# WidePhoton.net
KiCad netlist of a schematic drawn in EAGLE
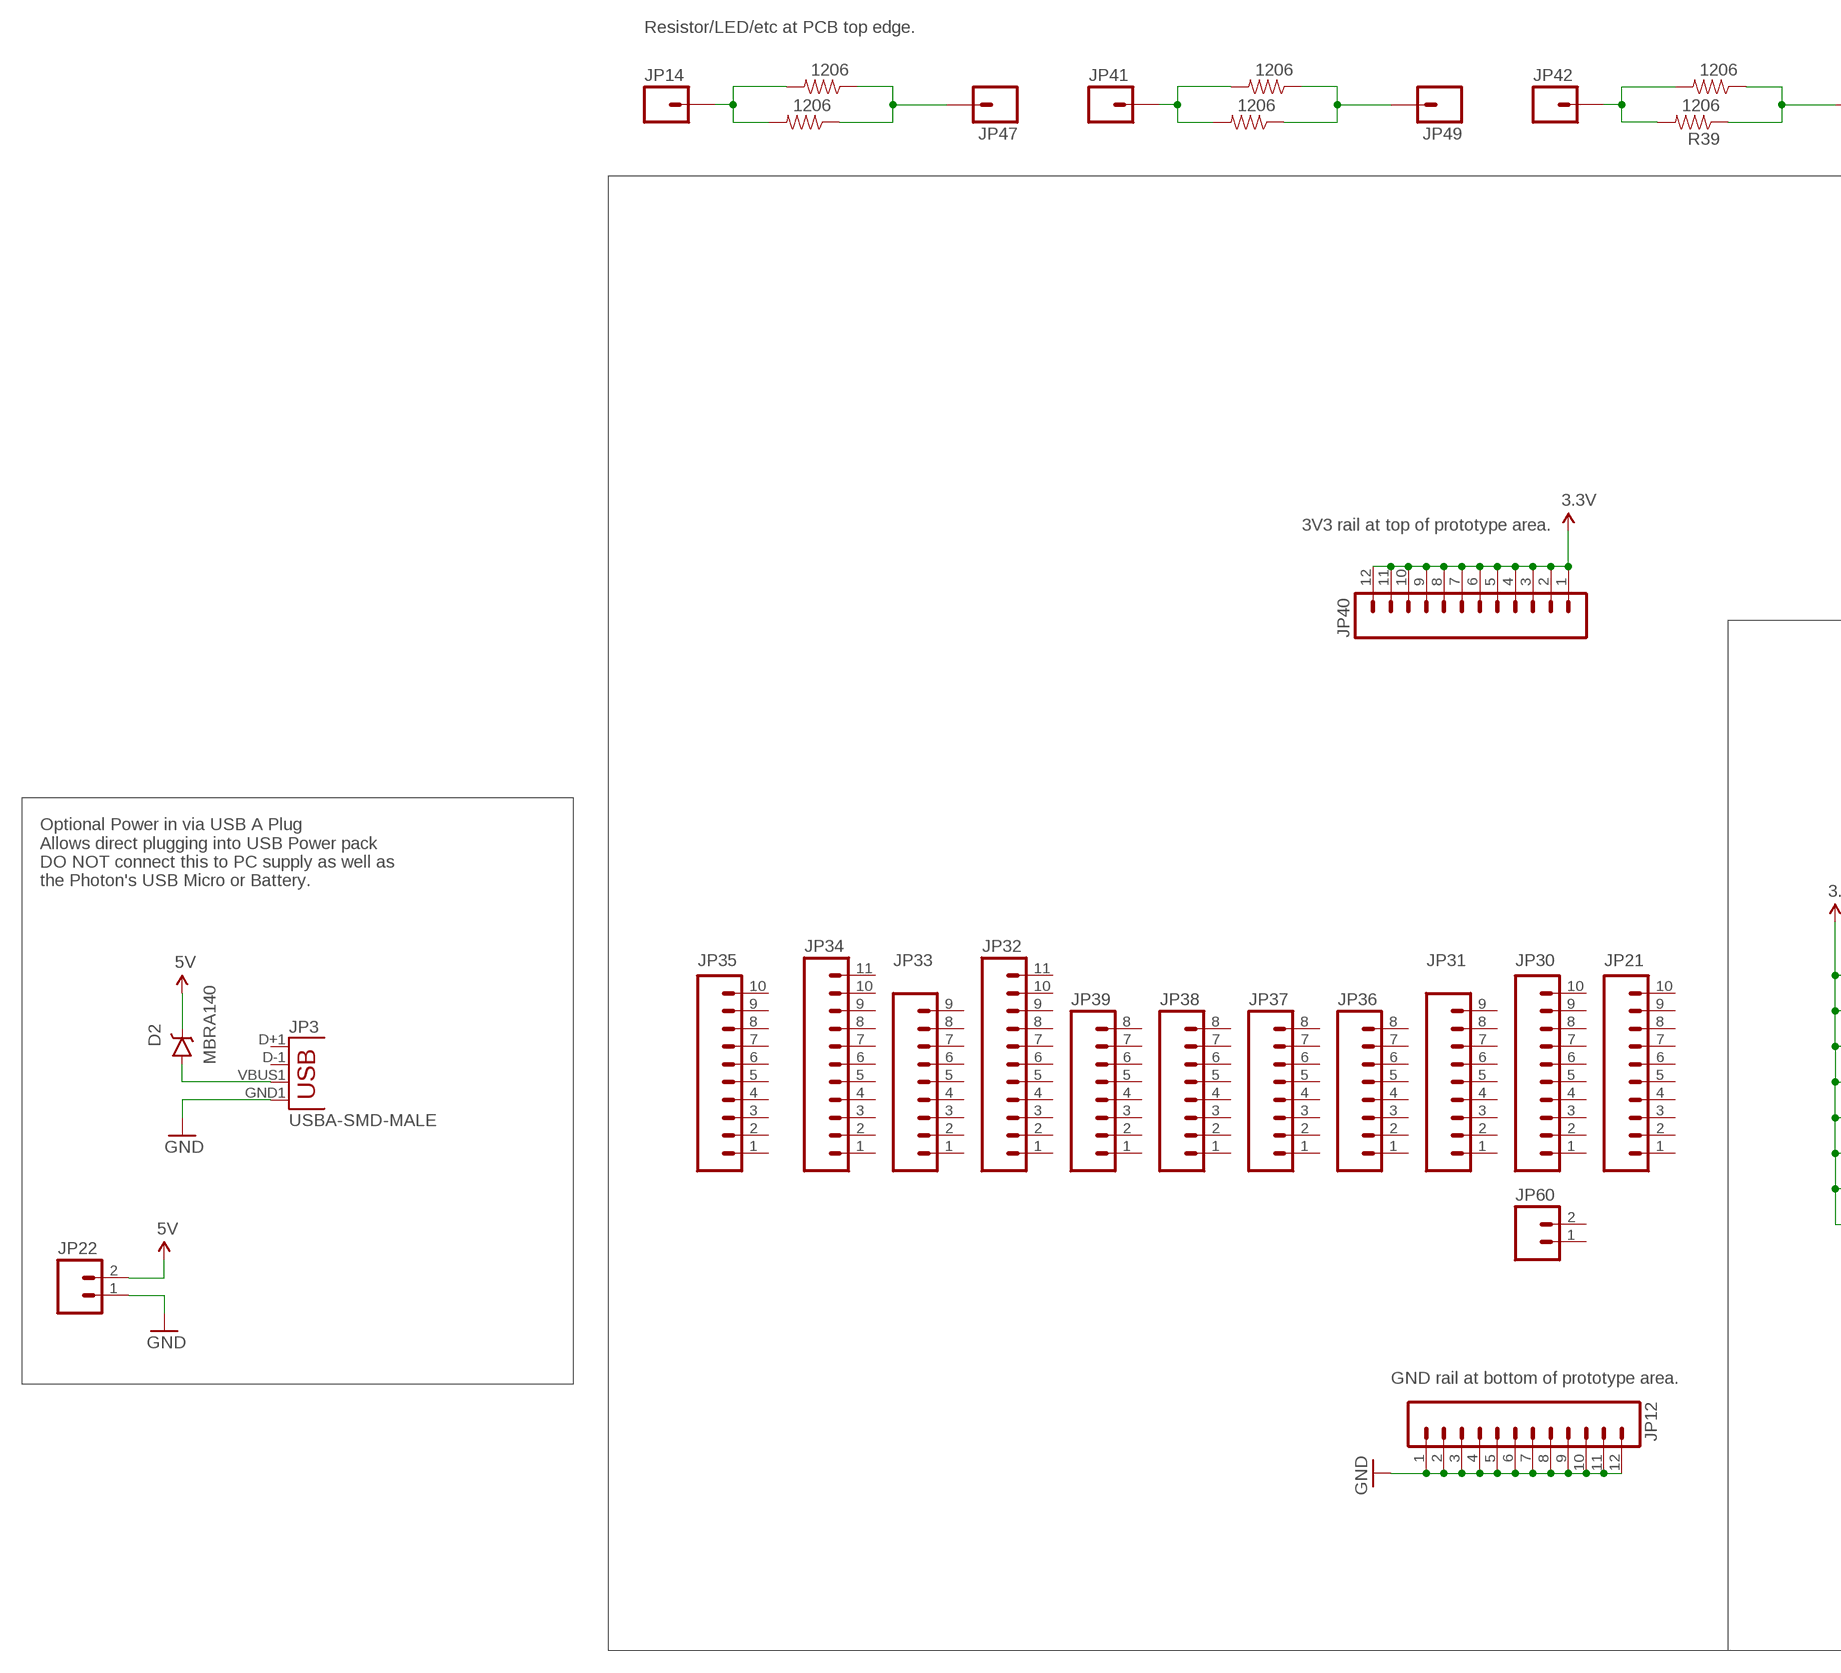
[diagram p0: schematic, sheet 1, part 1 of 2]
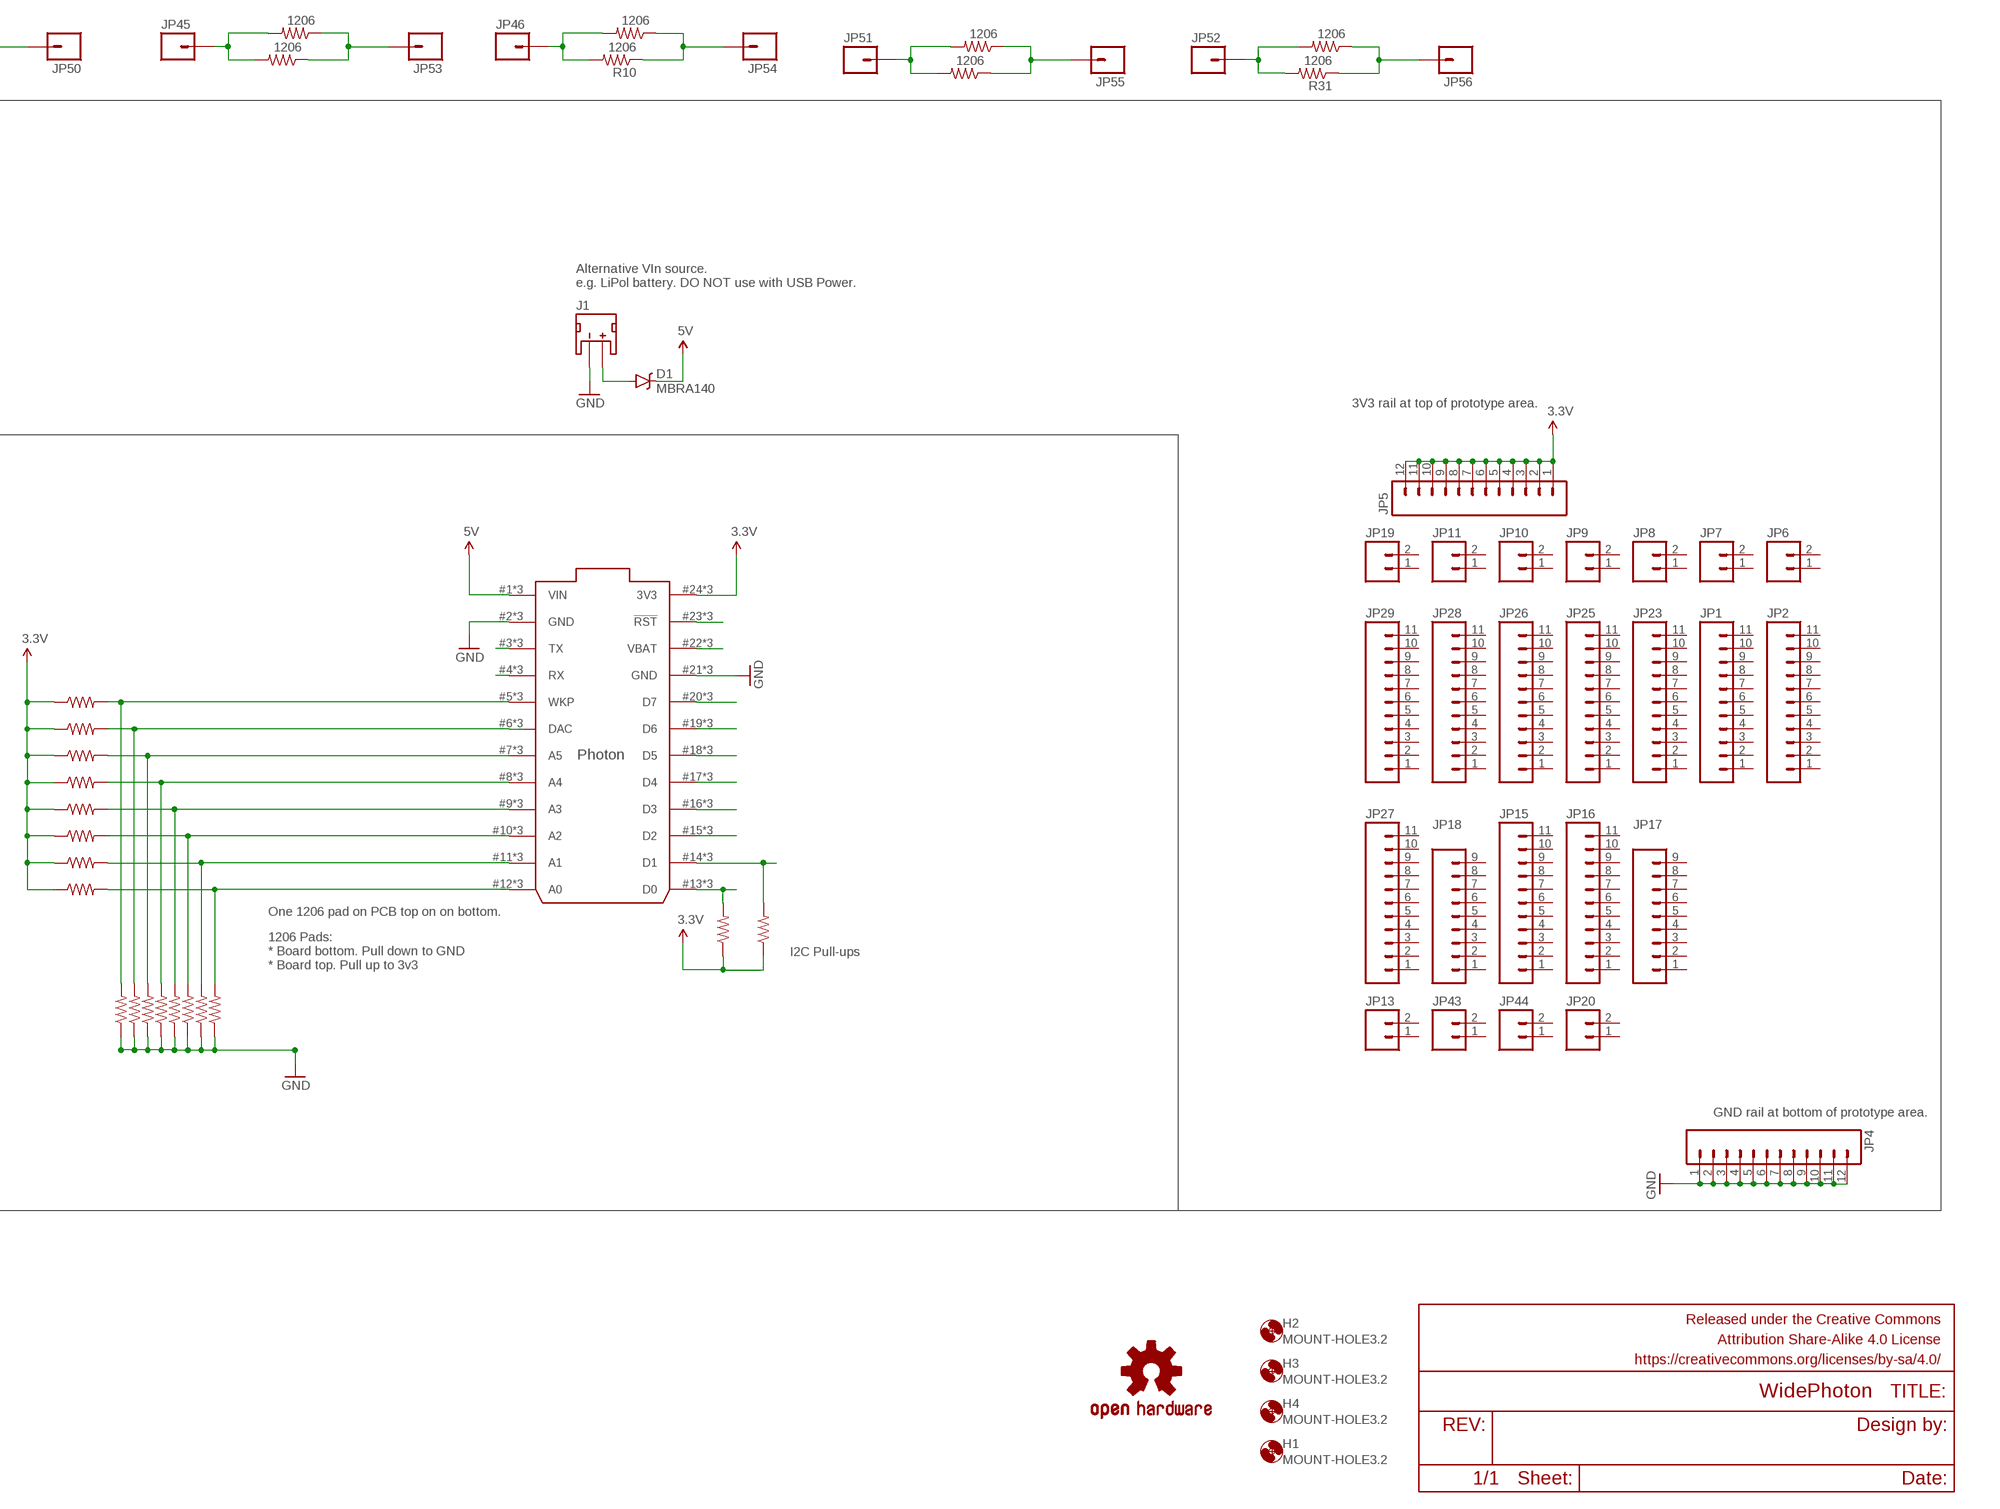
[diagram p1: schematic, sheet 1, part 2 of 2]

(export (version "E")
  (design (tool "Eeschema 10.0.6"))
  (components
    (comp (ref "D1")
      (value "MBRA140")
      (footprint "eagle-import:SMA-DIODE")
      (libsource (lib "eagle-import") (part "MBRA140"))
    )
    (comp (ref "D2")
      (value "MBRA140")
      (footprint "eagle-import:SMA-DIODE")
      (libsource (lib "eagle-import") (part "MBRA140"))
    )
    (comp (ref "FRAME1")
      (value "FRAME-LEDGER")
      (footprint "eagle-import:CREATIVE_COMMONS")
      (libsource (lib "eagle-import") (part "FRAME-LEDGER"))
    )
    (comp (ref "H1")
      (value "MOUNT-HOLE3.2")
      (footprint "eagle-import:3,2")
      (libsource (lib "eagle-import") (part "MOUNT-HOLE3.2"))
    )
    (comp (ref "H2")
      (value "MOUNT-HOLE3.2")
      (footprint "eagle-import:3,2")
      (libsource (lib "eagle-import") (part "MOUNT-HOLE3.2"))
    )
    (comp (ref "H3")
      (value "MOUNT-HOLE3.2")
      (footprint "eagle-import:3,2")
      (libsource (lib "eagle-import") (part "MOUNT-HOLE3.2"))
    )
    (comp (ref "H4")
      (value "MOUNT-HOLE3.2")
      (footprint "eagle-import:3,2")
      (libsource (lib "eagle-import") (part "MOUNT-HOLE3.2"))
    )
    (comp (ref "IC1")
      (value "PHOTON_WITH_STACKABLE_HEADERS")
      (footprint "eagle-import:PHOTON_STACKABLE")
      (libsource (lib "eagle-import") (part "PHOTON_WITH_STACKABLE_HEADERS"))
    )
    (comp (ref "J1")
      (value "JST_2MM_MALE")
      (footprint "eagle-import:JST-2-SMD")
      (libsource (lib "eagle-import") (part "JST_2MM_MALE"))
    )
    (comp (ref "JP1")
      (value "M111X11_NO_SILK")
      (footprint "eagle-import:1X11_NO_SILK")
      (libsource (lib "eagle-import") (part "M111X11_NO_SILK"))
    )
    (comp (ref "JP2")
      (value "M111X11_NO_SILK")
      (footprint "eagle-import:1X11_NO_SILK")
      (libsource (lib "eagle-import") (part "M111X11_NO_SILK"))
    )
    (comp (ref "JP3")
      (value "USBA-SMD-MALE")
      (footprint "eagle-import:USB-A-SMT-MALE")
      (libsource (lib "eagle-import") (part "USBA-SMD-MALE"))
    )
    (comp (ref "JP4")
      (value "M12PTH")
      (footprint "eagle-import:1X12")
      (libsource (lib "eagle-import") (part "M12PTH"))
    )
    (comp (ref "JP5")
      (value "M12PTH")
      (footprint "eagle-import:1X12")
      (libsource (lib "eagle-import") (part "M12PTH"))
    )
    (comp (ref "JP6")
      (value "M021X02_NO_SILK")
      (footprint "eagle-import:1X02_NO_SILK")
      (libsource (lib "eagle-import") (part "M021X02_NO_SILK"))
    )
    (comp (ref "JP7")
      (value "M021X02_NO_SILK")
      (footprint "eagle-import:1X02_NO_SILK")
      (libsource (lib "eagle-import") (part "M021X02_NO_SILK"))
    )
    (comp (ref "JP8")
      (value "M021X02_NO_SILK")
      (footprint "eagle-import:1X02_NO_SILK")
      (libsource (lib "eagle-import") (part "M021X02_NO_SILK"))
    )
    (comp (ref "JP9")
      (value "M021X02_NO_SILK")
      (footprint "eagle-import:1X02_NO_SILK")
      (libsource (lib "eagle-import") (part "M021X02_NO_SILK"))
    )
    (comp (ref "JP10")
      (value "M021X02_NO_SILK")
      (footprint "eagle-import:1X02_NO_SILK")
      (libsource (lib "eagle-import") (part "M021X02_NO_SILK"))
    )
    (comp (ref "JP11")
      (value "M021X02_NO_SILK")
      (footprint "eagle-import:1X02_NO_SILK")
      (libsource (lib "eagle-import") (part "M021X02_NO_SILK"))
    )
    (comp (ref "JP12")
      (value "M12PTH")
      (footprint "eagle-import:1X12")
      (libsource (lib "eagle-import") (part "M12PTH"))
    )
    (comp (ref "JP13")
      (value "M021X02_NO_SILK")
      (footprint "eagle-import:1X02_NO_SILK")
      (libsource (lib "eagle-import") (part "M021X02_NO_SILK"))
    )
    (comp (ref "JP14")
      (value "M01PTH")
      (footprint "eagle-import:1X01")
      (libsource (lib "eagle-import") (part "M01PTH"))
    )
    (comp (ref "JP15")
      (value "M111X11_NO_SILK")
      (footprint "eagle-import:1X11_NO_SILK")
      (libsource (lib "eagle-import") (part "M111X11_NO_SILK"))
    )
    (comp (ref "JP16")
      (value "M111X11_NO_SILK")
      (footprint "eagle-import:1X11_NO_SILK")
      (libsource (lib "eagle-import") (part "M111X11_NO_SILK"))
    )
    (comp (ref "JP17")
      (value "M09NO_SILK")
      (footprint "eagle-import:1X09_NO_SILK")
      (libsource (lib "eagle-import") (part "M09NO_SILK"))
    )
    (comp (ref "JP18")
      (value "M09NO_SILK")
      (footprint "eagle-import:1X09_NO_SILK")
      (libsource (lib "eagle-import") (part "M09NO_SILK"))
    )
    (comp (ref "JP19")
      (value "M021X02_NO_SILK")
      (footprint "eagle-import:1X02_NO_SILK")
      (libsource (lib "eagle-import") (part "M021X02_NO_SILK"))
    )
    (comp (ref "JP20")
      (value "M021X02_NO_SILK")
      (footprint "eagle-import:1X02_NO_SILK")
      (libsource (lib "eagle-import") (part "M021X02_NO_SILK"))
    )
    (comp (ref "JP21")
      (value "M10NO_SILK_PTH_FEMALE")
      (footprint "eagle-import:1X10_NO_SILK")
      (libsource (lib "eagle-import") (part "M10NO_SILK_PTH_FEMALE"))
    )
    (comp (ref "JP22")
      (value "M021X02_NO_SILK")
      (footprint "eagle-import:1X02_NO_SILK")
      (libsource (lib "eagle-import") (part "M021X02_NO_SILK"))
    )
    (comp (ref "JP23")
      (value "M111X11_NO_SILK")
      (footprint "eagle-import:1X11_NO_SILK")
      (libsource (lib "eagle-import") (part "M111X11_NO_SILK"))
    )
    (comp (ref "JP25")
      (value "M111X11_NO_SILK")
      (footprint "eagle-import:1X11_NO_SILK")
      (libsource (lib "eagle-import") (part "M111X11_NO_SILK"))
    )
    (comp (ref "JP26")
      (value "M111X11_NO_SILK")
      (footprint "eagle-import:1X11_NO_SILK")
      (libsource (lib "eagle-import") (part "M111X11_NO_SILK"))
    )
    (comp (ref "JP27")
      (value "M111X11_NO_SILK")
      (footprint "eagle-import:1X11_NO_SILK")
      (libsource (lib "eagle-import") (part "M111X11_NO_SILK"))
    )
    (comp (ref "JP28")
      (value "M111X11_NO_SILK")
      (footprint "eagle-import:1X11_NO_SILK")
      (libsource (lib "eagle-import") (part "M111X11_NO_SILK"))
    )
    (comp (ref "JP29")
      (value "M111X11_NO_SILK")
      (footprint "eagle-import:1X11_NO_SILK")
      (libsource (lib "eagle-import") (part "M111X11_NO_SILK"))
    )
    (comp (ref "JP30")
      (value "M10NO_SILK_PTH_FEMALE")
      (footprint "eagle-import:1X10_NO_SILK")
      (libsource (lib "eagle-import") (part "M10NO_SILK_PTH_FEMALE"))
    )
    (comp (ref "JP31")
      (value "M09NO_SILK")
      (footprint "eagle-import:1X09_NO_SILK")
      (libsource (lib "eagle-import") (part "M09NO_SILK"))
    )
    (comp (ref "JP32")
      (value "M111X11_NO_SILK")
      (footprint "eagle-import:1X11_NO_SILK")
      (libsource (lib "eagle-import") (part "M111X11_NO_SILK"))
    )
    (comp (ref "JP33")
      (value "M09NO_SILK")
      (footprint "eagle-import:1X09_NO_SILK")
      (libsource (lib "eagle-import") (part "M09NO_SILK"))
    )
    (comp (ref "JP34")
      (value "M111X11_NO_SILK")
      (footprint "eagle-import:1X11_NO_SILK")
      (libsource (lib "eagle-import") (part "M111X11_NO_SILK"))
    )
    (comp (ref "JP35")
      (value "M10NO_SILK_PTH_FEMALE")
      (footprint "eagle-import:1X10_NO_SILK")
      (libsource (lib "eagle-import") (part "M10NO_SILK_PTH_FEMALE"))
    )
    (comp (ref "JP36")
      (value "M08NO_SILK_FEMALE_PTH")
      (footprint "eagle-import:1X08_NO_SILK")
      (libsource (lib "eagle-import") (part "M08NO_SILK_FEMALE_PTH"))
    )
    (comp (ref "JP37")
      (value "M08NO_SILK_FEMALE_PTH")
      (footprint "eagle-import:1X08_NO_SILK")
      (libsource (lib "eagle-import") (part "M08NO_SILK_FEMALE_PTH"))
    )
    (comp (ref "JP38")
      (value "M08NO_SILK_FEMALE_PTH")
      (footprint "eagle-import:1X08_NO_SILK")
      (libsource (lib "eagle-import") (part "M08NO_SILK_FEMALE_PTH"))
    )
    (comp (ref "JP39")
      (value "M08NO_SILK_FEMALE_PTH")
      (footprint "eagle-import:1X08_NO_SILK")
      (libsource (lib "eagle-import") (part "M08NO_SILK_FEMALE_PTH"))
    )
    (comp (ref "JP40")
      (value "M12PTH")
      (footprint "eagle-import:1X12")
      (libsource (lib "eagle-import") (part "M12PTH"))
    )
    (comp (ref "JP41")
      (value "M01PTH")
      (footprint "eagle-import:1X01")
      (libsource (lib "eagle-import") (part "M01PTH"))
    )
    (comp (ref "JP42")
      (value "M01PTH")
      (footprint "eagle-import:1X01")
      (libsource (lib "eagle-import") (part "M01PTH"))
    )
    (comp (ref "JP43")
      (value "M021X02_NO_SILK")
      (footprint "eagle-import:1X02_NO_SILK")
      (libsource (lib "eagle-import") (part "M021X02_NO_SILK"))
    )
    (comp (ref "JP44")
      (value "M021X02_NO_SILK")
      (footprint "eagle-import:1X02_NO_SILK")
      (libsource (lib "eagle-import") (part "M021X02_NO_SILK"))
    )
    (comp (ref "JP45")
      (value "M01PTH")
      (footprint "eagle-import:1X01")
      (libsource (lib "eagle-import") (part "M01PTH"))
    )
    (comp (ref "JP46")
      (value "M01PTH")
      (footprint "eagle-import:1X01")
      (libsource (lib "eagle-import") (part "M01PTH"))
    )
    (comp (ref "JP47")
      (value "M01PTH")
      (footprint "eagle-import:1X01")
      (libsource (lib "eagle-import") (part "M01PTH"))
    )
    (comp (ref "JP49")
      (value "M01PTH")
      (footprint "eagle-import:1X01")
      (libsource (lib "eagle-import") (part "M01PTH"))
    )
    (comp (ref "JP50")
      (value "M01PTH")
      (footprint "eagle-import:1X01")
      (libsource (lib "eagle-import") (part "M01PTH"))
    )
    (comp (ref "JP51")
      (value "M01PTH")
      (footprint "eagle-import:1X01")
      (libsource (lib "eagle-import") (part "M01PTH"))
    )
    (comp (ref "JP52")
      (value "M01PTH")
      (footprint "eagle-import:1X01")
      (libsource (lib "eagle-import") (part "M01PTH"))
    )
    (comp (ref "JP53")
      (value "M01PTH")
      (footprint "eagle-import:1X01")
      (libsource (lib "eagle-import") (part "M01PTH"))
    )
    (comp (ref "JP54")
      (value "M01PTH")
      (footprint "eagle-import:1X01")
      (libsource (lib "eagle-import") (part "M01PTH"))
    )
    (comp (ref "JP55")
      (value "M01PTH")
      (footprint "eagle-import:1X01")
      (libsource (lib "eagle-import") (part "M01PTH"))
    )
    (comp (ref "JP56")
      (value "M01PTH")
      (footprint "eagle-import:1X01")
      (libsource (lib "eagle-import") (part "M01PTH"))
    )
    (comp (ref "JP60")
      (value "M021X02_NO_SILK")
      (footprint "eagle-import:1X02_NO_SILK")
      (libsource (lib "eagle-import") (part "M021X02_NO_SILK"))
    )
    (comp (ref "LOGO1")
      (value "OSHW-LOGOM")
      (footprint "eagle-import:OSHW-LOGO-M")
      (libsource (lib "eagle-import") (part "OSHW-LOGOM"))
    )
    (comp (ref "R1")
      (value "1206")
      (footprint "eagle-import:1206")
      (libsource (lib "eagle-import") (part "RESISTOR1206"))
    )
    (comp (ref "R2")
      (value "1206")
      (footprint "eagle-import:1206")
      (libsource (lib "eagle-import") (part "RESISTOR1206"))
    )
    (comp (ref "R3")
      (value "1206")
      (footprint "eagle-import:1206")
      (libsource (lib "eagle-import") (part "RESISTOR1206"))
    )
    (comp (ref "R4")
      (value "1206")
      (footprint "eagle-import:1206")
      (libsource (lib "eagle-import") (part "RESISTOR1206"))
    )
    (comp (ref "R5")
      (value "1206")
      (footprint "eagle-import:1206")
      (libsource (lib "eagle-import") (part "RESISTOR1206"))
    )
    (comp (ref "R6")
      (value "1206")
      (footprint "eagle-import:1206")
      (libsource (lib "eagle-import") (part "RESISTOR1206"))
    )
    (comp (ref "R7")
      (value "1206")
      (footprint "eagle-import:1206")
      (libsource (lib "eagle-import") (part "RESISTOR1206"))
    )
    (comp (ref "R8")
      (value "1206")
      (footprint "eagle-import:1206")
      (libsource (lib "eagle-import") (part "RESISTOR1206"))
    )
    (comp (ref "R9")
      (value "1206")
      (footprint "eagle-import:1206")
      (libsource (lib "eagle-import") (part "RESISTOR1206"))
    )
    (comp (ref "R10")
      (value "1206")
      (footprint "eagle-import:1206")
      (libsource (lib "eagle-import") (part "RESISTOR1206"))
    )
    (comp (ref "R12")
      (value "1206")
      (footprint "eagle-import:1206")
      (libsource (lib "eagle-import") (part "RESISTOR1206"))
    )
    (comp (ref "R13")
      (value "1206")
      (footprint "eagle-import:1206")
      (libsource (lib "eagle-import") (part "RESISTOR1206"))
    )
    (comp (ref "R14")
      (value "1206")
      (footprint "eagle-import:1206")
      (libsource (lib "eagle-import") (part "RESISTOR1206"))
    )
    (comp (ref "R15")
      (value "1206")
      (footprint "eagle-import:1206")
      (libsource (lib "eagle-import") (part "RESISTOR1206"))
    )
    (comp (ref "R16")
      (value "1206")
      (footprint "eagle-import:1206")
      (libsource (lib "eagle-import") (part "RESISTOR1206"))
    )
    (comp (ref "R17")
      (value "1206")
      (footprint "eagle-import:1206")
      (libsource (lib "eagle-import") (part "RESISTOR1206"))
    )
    (comp (ref "R19")
      (value "1206")
      (footprint "eagle-import:1206")
      (libsource (lib "eagle-import") (part "RESISTOR1206"))
    )
    (comp (ref "R20")
      (value "1206")
      (footprint "eagle-import:1206")
      (libsource (lib "eagle-import") (part "RESISTOR1206"))
    )
    (comp (ref "R21")
      (value "1206")
      (footprint "eagle-import:1206")
      (libsource (lib "eagle-import") (part "RESISTOR1206"))
    )
    (comp (ref "R22")
      (value "1206")
      (footprint "eagle-import:1206")
      (libsource (lib "eagle-import") (part "RESISTOR1206"))
    )
    (comp (ref "R24")
      (value "1206")
      (footprint "eagle-import:1206")
      (libsource (lib "eagle-import") (part "RESISTOR1206"))
    )
    (comp (ref "R30")
      (value "1206")
      (footprint "eagle-import:1206")
      (libsource (lib "eagle-import") (part "RESISTOR1206"))
    )
    (comp (ref "R31")
      (value "1206")
      (footprint "eagle-import:1206")
      (libsource (lib "eagle-import") (part "RESISTOR1206"))
    )
    (comp (ref "R32")
      (value "1206")
      (footprint "eagle-import:1206")
      (libsource (lib "eagle-import") (part "RESISTOR1206"))
    )
    (comp (ref "R34")
      (value "1206")
      (footprint "eagle-import:1206")
      (libsource (lib "eagle-import") (part "RESISTOR1206"))
    )
    (comp (ref "R35")
      (value "1206")
      (footprint "eagle-import:1206")
      (libsource (lib "eagle-import") (part "RESISTOR1206"))
    )
    (comp (ref "R36")
      (value "1206")
      (footprint "eagle-import:1206")
      (libsource (lib "eagle-import") (part "RESISTOR1206"))
    )
    (comp (ref "R37")
      (value "1206")
      (footprint "eagle-import:1206")
      (libsource (lib "eagle-import") (part "RESISTOR1206"))
    )
    (comp (ref "R39")
      (value "1206")
      (footprint "eagle-import:1206")
      (libsource (lib "eagle-import") (part "RESISTOR1206"))
    )
    (comp (ref "R40")
      (value "1206")
      (footprint "eagle-import:1206")
      (libsource (lib "eagle-import") (part "RESISTOR1206"))
    )
    (comp (ref "R41")
      (value "1206")
      (footprint "eagle-import:1206")
      (libsource (lib "eagle-import") (part "RESISTOR1206"))
    )
    (comp (ref "R44")
      (value "1206")
      (footprint "eagle-import:1206")
      (libsource (lib "eagle-import") (part "RESISTOR1206"))
    )
  )
  (nets
    (net (code "1") (name "3.3V") (class "Default")
      (node (ref "IC1") (pin "#24") (pinfunction "3V3_#24") (pintype "power_in"))
      (node (ref "IC1") (pin "24") (pinfunction "3V3_24") (pintype "power_in"))
      (node (ref "IC1") (pin "@24") (pinfunction "3V3_@24") (pintype "power_in"))
      (node (ref "JP40") (pin "1") (pinfunction "1_1") (pintype "passive"))
      (node (ref "JP40") (pin "10") (pinfunction "10_10") (pintype "passive"))
      (node (ref "JP40") (pin "11") (pinfunction "11_11") (pintype "passive"))
      (node (ref "JP40") (pin "12") (pinfunction "12_12") (pintype "passive"))
      (node (ref "JP40") (pin "2") (pinfunction "2_2") (pintype "passive"))
      (node (ref "JP40") (pin "3") (pinfunction "3_3") (pintype "passive"))
      (node (ref "JP40") (pin "4") (pinfunction "4_4") (pintype "passive"))
      (node (ref "JP40") (pin "5") (pinfunction "5_5") (pintype "passive"))
      (node (ref "JP40") (pin "6") (pinfunction "6_6") (pintype "passive"))
      (node (ref "JP40") (pin "7") (pinfunction "7_7") (pintype "passive"))
      (node (ref "JP40") (pin "8") (pinfunction "8_8") (pintype "passive"))
      (node (ref "JP40") (pin "9") (pinfunction "9_9") (pintype "passive"))
      (node (ref "JP5") (pin "1") (pinfunction "1_1") (pintype "passive"))
      (node (ref "JP5") (pin "10") (pinfunction "10_10") (pintype "passive"))
      (node (ref "JP5") (pin "11") (pinfunction "11_11") (pintype "passive"))
      (node (ref "JP5") (pin "12") (pinfunction "12_12") (pintype "passive"))
      (node (ref "JP5") (pin "2") (pinfunction "2_2") (pintype "passive"))
      (node (ref "JP5") (pin "3") (pinfunction "3_3") (pintype "passive"))
      (node (ref "JP5") (pin "4") (pinfunction "4_4") (pintype "passive"))
      (node (ref "JP5") (pin "5") (pinfunction "5_5") (pintype "passive"))
      (node (ref "JP5") (pin "6") (pinfunction "6_6") (pintype "passive"))
      (node (ref "JP5") (pin "7") (pinfunction "7_7") (pintype "passive"))
      (node (ref "JP5") (pin "8") (pinfunction "8_8") (pintype "passive"))
      (node (ref "JP5") (pin "9") (pinfunction "9_9") (pintype "passive"))
      (node (ref "R1") (pin "1") (pinfunction "1_1") (pintype "passive"))
      (node (ref "R12") (pin "1") (pinfunction "1_1") (pintype "passive"))
      (node (ref "R15") (pin "1") (pinfunction "1_1") (pintype "passive"))
      (node (ref "R2") (pin "1") (pinfunction "1_1") (pintype "passive"))
      (node (ref "R3") (pin "1") (pinfunction "1_1") (pintype "passive"))
      (node (ref "R4") (pin "1") (pinfunction "1_1") (pintype "passive"))
      (node (ref "R5") (pin "1") (pinfunction "1_1") (pintype "passive"))
      (node (ref "R6") (pin "1") (pinfunction "1_1") (pintype "passive"))
      (node (ref "R7") (pin "1") (pinfunction "1_1") (pintype "passive"))
      (node (ref "R9") (pin "1") (pinfunction "1_1") (pintype "passive"))
    )
    (net (code "2") (name "5V") (class "Default")
      (node (ref "D1") (pin "C") (pinfunction "C_C") (pintype "passive"))
      (node (ref "D2") (pin "C") (pinfunction "C_C") (pintype "passive"))
      (node (ref "IC1") (pin "#1") (pinfunction "VIN_#1") (pintype "power_in"))
      (node (ref "IC1") (pin "1") (pinfunction "VIN_1") (pintype "power_in"))
      (node (ref "IC1") (pin "@1") (pinfunction "VIN_@1") (pintype "power_in"))
      (node (ref "JP22") (pin "2") (pinfunction "2_2") (pintype "passive"))
    )
    (net (code "3") (name "GND") (class "Default")
      (node (ref "IC1") (pin "#2") (pinfunction "GND_#2") (pintype "power_in"))
      (node (ref "IC1") (pin "#21") (pinfunction "GND_#21") (pintype "power_in"))
      (node (ref "IC1") (pin "2") (pinfunction "GND_2") (pintype "power_in"))
      (node (ref "IC1") (pin "21") (pinfunction "GND_21") (pintype "power_in"))
      (node (ref "IC1") (pin "@2") (pinfunction "GND_@2") (pintype "power_in"))
      (node (ref "IC1") (pin "@21") (pinfunction "GND_@21") (pintype "power_in"))
      (node (ref "J1") (pin "1") (pinfunction "-_1") (pintype "bidirectional"))
      (node (ref "JP12") (pin "1") (pinfunction "1_1") (pintype "passive"))
      (node (ref "JP12") (pin "10") (pinfunction "10_10") (pintype "passive"))
      (node (ref "JP12") (pin "11") (pinfunction "11_11") (pintype "passive"))
      (node (ref "JP12") (pin "12") (pinfunction "12_12") (pintype "passive"))
      (node (ref "JP12") (pin "2") (pinfunction "2_2") (pintype "passive"))
      (node (ref "JP12") (pin "3") (pinfunction "3_3") (pintype "passive"))
      (node (ref "JP12") (pin "4") (pinfunction "4_4") (pintype "passive"))
      (node (ref "JP12") (pin "5") (pinfunction "5_5") (pintype "passive"))
      (node (ref "JP12") (pin "6") (pinfunction "6_6") (pintype "passive"))
      (node (ref "JP12") (pin "7") (pinfunction "7_7") (pintype "passive"))
      (node (ref "JP12") (pin "8") (pinfunction "8_8") (pintype "passive"))
      (node (ref "JP12") (pin "9") (pinfunction "9_9") (pintype "passive"))
      (node (ref "JP22") (pin "1") (pinfunction "1_1") (pintype "passive"))
      (node (ref "JP3") (pin "GND1") (pinfunction "GND_GND1") (pintype "bidirectional"))
      (node (ref "JP4") (pin "1") (pinfunction "1_1") (pintype "passive"))
      (node (ref "JP4") (pin "10") (pinfunction "10_10") (pintype "passive"))
      (node (ref "JP4") (pin "11") (pinfunction "11_11") (pintype "passive"))
      (node (ref "JP4") (pin "12") (pinfunction "12_12") (pintype "passive"))
      (node (ref "JP4") (pin "2") (pinfunction "2_2") (pintype "passive"))
      (node (ref "JP4") (pin "3") (pinfunction "3_3") (pintype "passive"))
      (node (ref "JP4") (pin "4") (pinfunction "4_4") (pintype "passive"))
      (node (ref "JP4") (pin "5") (pinfunction "5_5") (pintype "passive"))
      (node (ref "JP4") (pin "6") (pinfunction "6_6") (pintype "passive"))
      (node (ref "JP4") (pin "7") (pinfunction "7_7") (pintype "passive"))
      (node (ref "JP4") (pin "8") (pinfunction "8_8") (pintype "passive"))
      (node (ref "JP4") (pin "9") (pinfunction "9_9") (pintype "passive"))
      (node (ref "R13") (pin "1") (pinfunction "1_1") (pintype "passive"))
      (node (ref "R14") (pin "1") (pinfunction "1_1") (pintype "passive"))
      (node (ref "R16") (pin "1") (pinfunction "1_1") (pintype "passive"))
      (node (ref "R19") (pin "1") (pinfunction "1_1") (pintype "passive"))
      (node (ref "R20") (pin "1") (pinfunction "1_1") (pintype "passive"))
      (node (ref "R21") (pin "1") (pinfunction "1_1") (pintype "passive"))
      (node (ref "R22") (pin "1") (pinfunction "1_1") (pintype "passive"))
      (node (ref "R8") (pin "1") (pinfunction "1_1") (pintype "passive"))
    )
    (net (code "4") (name "Net-(IC1-A0-Pad#12)") (class "Default")
      (node (ref "IC1") (pin "#12") (pinfunction "A0_#12") (pintype "bidirectional"))
      (node (ref "IC1") (pin "12") (pinfunction "A0_12") (pintype "bidirectional"))
      (node (ref "IC1") (pin "@12") (pinfunction "A0_@12") (pintype "bidirectional"))
      (node (ref "R22") (pin "2") (pinfunction "2_2") (pintype "passive"))
      (node (ref "R7") (pin "2") (pinfunction "2_2") (pintype "passive"))
    )
    (net (code "5") (name "Net-(IC1-A1-Pad#11)") (class "Default")
      (node (ref "IC1") (pin "#11") (pinfunction "A1_#11") (pintype "bidirectional"))
      (node (ref "IC1") (pin "11") (pinfunction "A1_11") (pintype "bidirectional"))
      (node (ref "IC1") (pin "@11") (pinfunction "A1_@11") (pintype "bidirectional"))
      (node (ref "R21") (pin "2") (pinfunction "2_2") (pintype "passive"))
      (node (ref "R6") (pin "2") (pinfunction "2_2") (pintype "passive"))
    )
    (net (code "6") (name "Net-(IC1-A2-Pad#10)") (class "Default")
      (node (ref "IC1") (pin "#10") (pinfunction "A2_#10") (pintype "bidirectional"))
      (node (ref "IC1") (pin "10") (pinfunction "A2_10") (pintype "bidirectional"))
      (node (ref "IC1") (pin "@10") (pinfunction "A2_@10") (pintype "bidirectional"))
      (node (ref "R20") (pin "2") (pinfunction "2_2") (pintype "passive"))
      (node (ref "R4") (pin "2") (pinfunction "2_2") (pintype "passive"))
    )
    (net (code "7") (name "Net-(IC1-A3-Pad#9)") (class "Default")
      (node (ref "IC1") (pin "#9") (pinfunction "A3_#9") (pintype "bidirectional"))
      (node (ref "IC1") (pin "9") (pinfunction "A3_9") (pintype "bidirectional"))
      (node (ref "IC1") (pin "@9") (pinfunction "A3_@9") (pintype "bidirectional"))
      (node (ref "R19") (pin "2") (pinfunction "2_2") (pintype "passive"))
      (node (ref "R3") (pin "2") (pinfunction "2_2") (pintype "passive"))
    )
    (net (code "8") (name "Net-(IC1-A4-Pad#8)") (class "Default")
      (node (ref "IC1") (pin "#8") (pinfunction "A4_#8") (pintype "bidirectional"))
      (node (ref "IC1") (pin "8") (pinfunction "A4_8") (pintype "bidirectional"))
      (node (ref "IC1") (pin "@8") (pinfunction "A4_@8") (pintype "bidirectional"))
      (node (ref "R14") (pin "2") (pinfunction "2_2") (pintype "passive"))
      (node (ref "R2") (pin "2") (pinfunction "2_2") (pintype "passive"))
    )
    (net (code "9") (name "Net-(IC1-A5-Pad#7)") (class "Default")
      (node (ref "IC1") (pin "#7") (pinfunction "A5_#7") (pintype "bidirectional"))
      (node (ref "IC1") (pin "7") (pinfunction "A5_7") (pintype "bidirectional"))
      (node (ref "IC1") (pin "@7") (pinfunction "A5_@7") (pintype "bidirectional"))
      (node (ref "R1") (pin "2") (pinfunction "2_2") (pintype "passive"))
      (node (ref "R13") (pin "2") (pinfunction "2_2") (pintype "passive"))
    )
    (net (code "10") (name "Net-(IC1-D0-Pad#13)") (class "Default")
      (node (ref "IC1") (pin "#13") (pinfunction "D0_#13") (pintype "bidirectional"))
      (node (ref "IC1") (pin "13") (pinfunction "D0_13") (pintype "bidirectional"))
      (node (ref "IC1") (pin "@13") (pinfunction "D0_@13") (pintype "bidirectional"))
      (node (ref "R5") (pin "2") (pinfunction "2_2") (pintype "passive"))
    )
    (net (code "11") (name "Net-(IC1-D1-Pad#14)") (class "Default")
      (node (ref "IC1") (pin "#14") (pinfunction "D1_#14") (pintype "bidirectional"))
      (node (ref "IC1") (pin "14") (pinfunction "D1_14") (pintype "bidirectional"))
      (node (ref "IC1") (pin "@14") (pinfunction "D1_@14") (pintype "bidirectional"))
      (node (ref "R9") (pin "2") (pinfunction "2_2") (pintype "passive"))
    )
    (net (code "12") (name "Net-(IC1-D2-Pad#15)") (class "Default")
      (node (ref "IC1") (pin "#15") (pinfunction "D2_#15") (pintype "bidirectional"))
      (node (ref "IC1") (pin "15") (pinfunction "D2_15") (pintype "bidirectional"))
      (node (ref "IC1") (pin "@15") (pinfunction "D2_@15") (pintype "bidirectional"))
    )
    (net (code "13") (name "Net-(IC1-D3-Pad#16)") (class "Default")
      (node (ref "IC1") (pin "#16") (pinfunction "D3_#16") (pintype "bidirectional"))
      (node (ref "IC1") (pin "16") (pinfunction "D3_16") (pintype "bidirectional"))
      (node (ref "IC1") (pin "@16") (pinfunction "D3_@16") (pintype "bidirectional"))
    )
    (net (code "14") (name "Net-(IC1-D4-Pad#17)") (class "Default")
      (node (ref "IC1") (pin "#17") (pinfunction "D4_#17") (pintype "bidirectional"))
      (node (ref "IC1") (pin "17") (pinfunction "D4_17") (pintype "bidirectional"))
      (node (ref "IC1") (pin "@17") (pinfunction "D4_@17") (pintype "bidirectional"))
    )
    (net (code "15") (name "Net-(IC1-D5-Pad#18)") (class "Default")
      (node (ref "IC1") (pin "#18") (pinfunction "D5_#18") (pintype "bidirectional"))
      (node (ref "IC1") (pin "18") (pinfunction "D5_18") (pintype "bidirectional"))
      (node (ref "IC1") (pin "@18") (pinfunction "D5_@18") (pintype "bidirectional"))
    )
    (net (code "16") (name "Net-(IC1-D6-Pad#19)") (class "Default")
      (node (ref "IC1") (pin "#19") (pinfunction "D6_#19") (pintype "bidirectional"))
      (node (ref "IC1") (pin "19") (pinfunction "D6_19") (pintype "bidirectional"))
      (node (ref "IC1") (pin "@19") (pinfunction "D6_@19") (pintype "bidirectional"))
    )
    (net (code "17") (name "Net-(IC1-D7-Pad#20)") (class "Default")
      (node (ref "IC1") (pin "#20") (pinfunction "D7_#20") (pintype "bidirectional"))
      (node (ref "IC1") (pin "20") (pinfunction "D7_20") (pintype "bidirectional"))
      (node (ref "IC1") (pin "@20") (pinfunction "D7_@20") (pintype "bidirectional"))
    )
    (net (code "18") (name "Net-(IC1-DAC-Pad#6)") (class "Default")
      (node (ref "IC1") (pin "#6") (pinfunction "DAC_#6") (pintype "bidirectional"))
      (node (ref "IC1") (pin "6") (pinfunction "DAC_6") (pintype "bidirectional"))
      (node (ref "IC1") (pin "@6") (pinfunction "DAC_@6") (pintype "bidirectional"))
      (node (ref "R15") (pin "2") (pinfunction "2_2") (pintype "passive"))
      (node (ref "R16") (pin "2") (pinfunction "2_2") (pintype "passive"))
    )
    (net (code "19") (name "Net-(IC1-RX-Pad#4)") (class "Default")
      (node (ref "IC1") (pin "#4") (pinfunction "RX_#4") (pintype "bidirectional"))
      (node (ref "IC1") (pin "4") (pinfunction "RX_4") (pintype "bidirectional"))
      (node (ref "IC1") (pin "@4") (pinfunction "RX_@4") (pintype "bidirectional"))
    )
    (net (code "20") (name "Net-(IC1-TX-Pad#3)") (class "Default")
      (node (ref "IC1") (pin "#3") (pinfunction "TX_#3") (pintype "bidirectional"))
      (node (ref "IC1") (pin "3") (pinfunction "TX_3") (pintype "bidirectional"))
      (node (ref "IC1") (pin "@3") (pinfunction "TX_@3") (pintype "bidirectional"))
    )
    (net (code "21") (name "Net-(IC1-VBAT-Pad#22)") (class "Default")
      (node (ref "IC1") (pin "#22") (pinfunction "VBAT_#22") (pintype "power_in"))
      (node (ref "IC1") (pin "22") (pinfunction "VBAT_22") (pintype "power_in"))
      (node (ref "IC1") (pin "@22") (pinfunction "VBAT_@22") (pintype "power_in"))
    )
    (net (code "22") (name "Net-(IC1-WKP-Pad#5)") (class "Default")
      (node (ref "IC1") (pin "#5") (pinfunction "WKP_#5") (pintype "bidirectional"))
      (node (ref "IC1") (pin "5") (pinfunction "WKP_5") (pintype "bidirectional"))
      (node (ref "IC1") (pin "@5") (pinfunction "WKP_@5") (pintype "bidirectional"))
      (node (ref "R12") (pin "2") (pinfunction "2_2") (pintype "passive"))
      (node (ref "R8") (pin "2") (pinfunction "2_2") (pintype "passive"))
    )
    (net (code "23") (name "Net-(IC1-~{RST}-Pad#23)") (class "Default")
      (node (ref "IC1") (pin "#23") (pinfunction "~{RST}_#23") (pintype "bidirectional"))
      (node (ref "IC1") (pin "23") (pinfunction "~{RST}_23") (pintype "bidirectional"))
      (node (ref "IC1") (pin "@23") (pinfunction "~{RST}_@23") (pintype "bidirectional"))
    )
    (net (code "24") (name "Net-(J1-+)") (class "Default")
      (node (ref "D1") (pin "A") (pinfunction "A_A") (pintype "passive"))
      (node (ref "J1") (pin "2") (pinfunction "+_2") (pintype "bidirectional"))
    )
    (net (code "25") (name "Net-(JP3-VBUS)") (class "Default")
      (node (ref "D2") (pin "A") (pinfunction "A_A") (pintype "passive"))
      (node (ref "JP3") (pin "VBUS1") (pinfunction "VBUS_VBUS1") (pintype "bidirectional"))
    )
    (net (code "26") (name "Net-(JP14-Pad1)") (class "Default")
      (node (ref "JP14") (pin "1") (pinfunction "1_1") (pintype "passive"))
      (node (ref "R34") (pin "2") (pinfunction "2_2") (pintype "passive"))
      (node (ref "R35") (pin "2") (pinfunction "2_2") (pintype "passive"))
    )
    (net (code "27") (name "Net-(JP41-Pad1)") (class "Default")
      (node (ref "JP41") (pin "1") (pinfunction "1_1") (pintype "passive"))
      (node (ref "R40") (pin "2") (pinfunction "2_2") (pintype "passive"))
      (node (ref "R41") (pin "2") (pinfunction "2_2") (pintype "passive"))
    )
    (net (code "28") (name "Net-(JP42-Pad1)") (class "Default")
      (node (ref "JP42") (pin "1") (pinfunction "1_1") (pintype "passive"))
      (node (ref "R39") (pin "2") (pinfunction "2_2") (pintype "passive"))
      (node (ref "R44") (pin "2") (pinfunction "2_2") (pintype "passive"))
    )
    (net (code "29") (name "Net-(JP45-Pad1)") (class "Default")
      (node (ref "JP45") (pin "1") (pinfunction "1_1") (pintype "passive"))
      (node (ref "R17") (pin "2") (pinfunction "2_2") (pintype "passive"))
      (node (ref "R24") (pin "2") (pinfunction "2_2") (pintype "passive"))
    )
    (net (code "30") (name "Net-(JP46-Pad1)") (class "Default")
      (node (ref "JP46") (pin "1") (pinfunction "1_1") (pintype "passive"))
      (node (ref "R10") (pin "2") (pinfunction "2_2") (pintype "passive"))
      (node (ref "R30") (pin "2") (pinfunction "2_2") (pintype "passive"))
    )
    (net (code "31") (name "Net-(JP47-Pad1)") (class "Default")
      (node (ref "JP47") (pin "1") (pinfunction "1_1") (pintype "passive"))
      (node (ref "R34") (pin "1") (pinfunction "1_1") (pintype "passive"))
      (node (ref "R35") (pin "1") (pinfunction "1_1") (pintype "passive"))
    )
    (net (code "32") (name "Net-(JP49-Pad1)") (class "Default")
      (node (ref "JP49") (pin "1") (pinfunction "1_1") (pintype "passive"))
      (node (ref "R40") (pin "1") (pinfunction "1_1") (pintype "passive"))
      (node (ref "R41") (pin "1") (pinfunction "1_1") (pintype "passive"))
    )
    (net (code "33") (name "Net-(JP50-Pad1)") (class "Default")
      (node (ref "JP50") (pin "1") (pinfunction "1_1") (pintype "passive"))
      (node (ref "R39") (pin "1") (pinfunction "1_1") (pintype "passive"))
      (node (ref "R44") (pin "1") (pinfunction "1_1") (pintype "passive"))
    )
    (net (code "34") (name "Net-(JP51-Pad1)") (class "Default")
      (node (ref "JP51") (pin "1") (pinfunction "1_1") (pintype "passive"))
      (node (ref "R32") (pin "2") (pinfunction "2_2") (pintype "passive"))
      (node (ref "R36") (pin "2") (pinfunction "2_2") (pintype "passive"))
    )
    (net (code "35") (name "Net-(JP52-Pad1)") (class "Default")
      (node (ref "JP52") (pin "1") (pinfunction "1_1") (pintype "passive"))
      (node (ref "R31") (pin "2") (pinfunction "2_2") (pintype "passive"))
      (node (ref "R37") (pin "2") (pinfunction "2_2") (pintype "passive"))
    )
    (net (code "36") (name "Net-(JP53-Pad1)") (class "Default")
      (node (ref "JP53") (pin "1") (pinfunction "1_1") (pintype "passive"))
      (node (ref "R17") (pin "1") (pinfunction "1_1") (pintype "passive"))
      (node (ref "R24") (pin "1") (pinfunction "1_1") (pintype "passive"))
    )
    (net (code "37") (name "Net-(JP54-Pad1)") (class "Default")
      (node (ref "JP54") (pin "1") (pinfunction "1_1") (pintype "passive"))
      (node (ref "R10") (pin "1") (pinfunction "1_1") (pintype "passive"))
      (node (ref "R30") (pin "1") (pinfunction "1_1") (pintype "passive"))
    )
    (net (code "38") (name "Net-(JP55-Pad1)") (class "Default")
      (node (ref "JP55") (pin "1") (pinfunction "1_1") (pintype "passive"))
      (node (ref "R32") (pin "1") (pinfunction "1_1") (pintype "passive"))
      (node (ref "R36") (pin "1") (pinfunction "1_1") (pintype "passive"))
    )
    (net (code "39") (name "Net-(JP56-Pad1)") (class "Default")
      (node (ref "JP56") (pin "1") (pinfunction "1_1") (pintype "passive"))
      (node (ref "R31") (pin "1") (pinfunction "1_1") (pintype "passive"))
      (node (ref "R37") (pin "1") (pinfunction "1_1") (pintype "passive"))
    )
    (net (code "40") (name "unconnected-(J1-PAD1-PadNC1)") (class "Default")
      (node (ref "J1") (pin "NC1") (pinfunction "PAD1_NC1") (pintype "bidirectional"))
    )
    (net (code "41") (name "unconnected-(J1-PAD2-PadNC2)") (class "Default")
      (node (ref "J1") (pin "NC2") (pinfunction "PAD2_NC2") (pintype "bidirectional"))
    )
    (net (code "42") (name "unconnected-(JP1-Pad1)") (class "Default")
      (node (ref "JP1") (pin "1") (pinfunction "1_1") (pintype "passive"))
    )
    (net (code "43") (name "unconnected-(JP1-Pad2)") (class "Default")
      (node (ref "JP1") (pin "2") (pinfunction "2_2") (pintype "passive"))
    )
    (net (code "44") (name "unconnected-(JP1-Pad3)") (class "Default")
      (node (ref "JP1") (pin "3") (pinfunction "3_3") (pintype "passive"))
    )
    (net (code "45") (name "unconnected-(JP1-Pad4)") (class "Default")
      (node (ref "JP1") (pin "4") (pinfunction "4_4") (pintype "passive"))
    )
    (net (code "46") (name "unconnected-(JP1-Pad5)") (class "Default")
      (node (ref "JP1") (pin "5") (pinfunction "5_5") (pintype "passive"))
    )
    (net (code "47") (name "unconnected-(JP1-Pad6)") (class "Default")
      (node (ref "JP1") (pin "6") (pinfunction "6_6") (pintype "passive"))
    )
    (net (code "48") (name "unconnected-(JP1-Pad7)") (class "Default")
      (node (ref "JP1") (pin "7") (pinfunction "7_7") (pintype "passive"))
    )
    (net (code "49") (name "unconnected-(JP1-Pad8)") (class "Default")
      (node (ref "JP1") (pin "8") (pinfunction "8_8") (pintype "passive"))
    )
    (net (code "50") (name "unconnected-(JP1-Pad9)") (class "Default")
      (node (ref "JP1") (pin "9") (pinfunction "9_9") (pintype "passive"))
    )
    (net (code "51") (name "unconnected-(JP1-Pad10)") (class "Default")
      (node (ref "JP1") (pin "10") (pinfunction "10_10") (pintype "passive"))
    )
    (net (code "52") (name "unconnected-(JP1-Pad11)") (class "Default")
      (node (ref "JP1") (pin "11") (pinfunction "11_11") (pintype "passive"))
    )
    (net (code "53") (name "unconnected-(JP2-Pad1)") (class "Default")
      (node (ref "JP2") (pin "1") (pinfunction "1_1") (pintype "passive"))
    )
    (net (code "54") (name "unconnected-(JP2-Pad2)") (class "Default")
      (node (ref "JP2") (pin "2") (pinfunction "2_2") (pintype "passive"))
    )
    (net (code "55") (name "unconnected-(JP2-Pad3)") (class "Default")
      (node (ref "JP2") (pin "3") (pinfunction "3_3") (pintype "passive"))
    )
    (net (code "56") (name "unconnected-(JP2-Pad4)") (class "Default")
      (node (ref "JP2") (pin "4") (pinfunction "4_4") (pintype "passive"))
    )
    (net (code "57") (name "unconnected-(JP2-Pad5)") (class "Default")
      (node (ref "JP2") (pin "5") (pinfunction "5_5") (pintype "passive"))
    )
    (net (code "58") (name "unconnected-(JP2-Pad6)") (class "Default")
      (node (ref "JP2") (pin "6") (pinfunction "6_6") (pintype "passive"))
    )
    (net (code "59") (name "unconnected-(JP2-Pad7)") (class "Default")
      (node (ref "JP2") (pin "7") (pinfunction "7_7") (pintype "passive"))
    )
    (net (code "60") (name "unconnected-(JP2-Pad8)") (class "Default")
      (node (ref "JP2") (pin "8") (pinfunction "8_8") (pintype "passive"))
    )
    (net (code "61") (name "unconnected-(JP2-Pad9)") (class "Default")
      (node (ref "JP2") (pin "9") (pinfunction "9_9") (pintype "passive"))
    )
    (net (code "62") (name "unconnected-(JP2-Pad10)") (class "Default")
      (node (ref "JP2") (pin "10") (pinfunction "10_10") (pintype "passive"))
    )
    (net (code "63") (name "unconnected-(JP2-Pad11)") (class "Default")
      (node (ref "JP2") (pin "11") (pinfunction "11_11") (pintype "passive"))
    )
    (net (code "64") (name "unconnected-(JP3-D+-PadD+1)") (class "Default")
      (node (ref "JP3") (pin "D+1") (pinfunction "D+_D+1") (pintype "bidirectional"))
    )
    (net (code "65") (name "unconnected-(JP3-D--PadD-1)") (class "Default")
      (node (ref "JP3") (pin "D-1") (pinfunction "D-_D-1") (pintype "bidirectional"))
    )
    (net (code "66") (name "unconnected-(JP6-Pad1)") (class "Default")
      (node (ref "JP6") (pin "1") (pinfunction "1_1") (pintype "passive"))
    )
    (net (code "67") (name "unconnected-(JP6-Pad2)") (class "Default")
      (node (ref "JP6") (pin "2") (pinfunction "2_2") (pintype "passive"))
    )
    (net (code "68") (name "unconnected-(JP7-Pad1)") (class "Default")
      (node (ref "JP7") (pin "1") (pinfunction "1_1") (pintype "passive"))
    )
    (net (code "69") (name "unconnected-(JP7-Pad2)") (class "Default")
      (node (ref "JP7") (pin "2") (pinfunction "2_2") (pintype "passive"))
    )
    (net (code "70") (name "unconnected-(JP8-Pad1)") (class "Default")
      (node (ref "JP8") (pin "1") (pinfunction "1_1") (pintype "passive"))
    )
    (net (code "71") (name "unconnected-(JP8-Pad2)") (class "Default")
      (node (ref "JP8") (pin "2") (pinfunction "2_2") (pintype "passive"))
    )
    (net (code "72") (name "unconnected-(JP9-Pad1)") (class "Default")
      (node (ref "JP9") (pin "1") (pinfunction "1_1") (pintype "passive"))
    )
    (net (code "73") (name "unconnected-(JP9-Pad2)") (class "Default")
      (node (ref "JP9") (pin "2") (pinfunction "2_2") (pintype "passive"))
    )
    (net (code "74") (name "unconnected-(JP10-Pad1)") (class "Default")
      (node (ref "JP10") (pin "1") (pinfunction "1_1") (pintype "passive"))
    )
    (net (code "75") (name "unconnected-(JP10-Pad2)") (class "Default")
      (node (ref "JP10") (pin "2") (pinfunction "2_2") (pintype "passive"))
    )
    (net (code "76") (name "unconnected-(JP11-Pad1)") (class "Default")
      (node (ref "JP11") (pin "1") (pinfunction "1_1") (pintype "passive"))
    )
    (net (code "77") (name "unconnected-(JP11-Pad2)") (class "Default")
      (node (ref "JP11") (pin "2") (pinfunction "2_2") (pintype "passive"))
    )
    (net (code "78") (name "unconnected-(JP13-Pad1)") (class "Default")
      (node (ref "JP13") (pin "1") (pinfunction "1_1") (pintype "passive"))
    )
    (net (code "79") (name "unconnected-(JP13-Pad2)") (class "Default")
      (node (ref "JP13") (pin "2") (pinfunction "2_2") (pintype "passive"))
    )
    (net (code "80") (name "unconnected-(JP15-Pad1)") (class "Default")
      (node (ref "JP15") (pin "1") (pinfunction "1_1") (pintype "passive"))
    )
    (net (code "81") (name "unconnected-(JP15-Pad2)") (class "Default")
      (node (ref "JP15") (pin "2") (pinfunction "2_2") (pintype "passive"))
    )
    (net (code "82") (name "unconnected-(JP15-Pad3)") (class "Default")
      (node (ref "JP15") (pin "3") (pinfunction "3_3") (pintype "passive"))
    )
    (net (code "83") (name "unconnected-(JP15-Pad4)") (class "Default")
      (node (ref "JP15") (pin "4") (pinfunction "4_4") (pintype "passive"))
    )
    (net (code "84") (name "unconnected-(JP15-Pad5)") (class "Default")
      (node (ref "JP15") (pin "5") (pinfunction "5_5") (pintype "passive"))
    )
    (net (code "85") (name "unconnected-(JP15-Pad6)") (class "Default")
      (node (ref "JP15") (pin "6") (pinfunction "6_6") (pintype "passive"))
    )
    (net (code "86") (name "unconnected-(JP15-Pad7)") (class "Default")
      (node (ref "JP15") (pin "7") (pinfunction "7_7") (pintype "passive"))
    )
    (net (code "87") (name "unconnected-(JP15-Pad8)") (class "Default")
      (node (ref "JP15") (pin "8") (pinfunction "8_8") (pintype "passive"))
    )
    (net (code "88") (name "unconnected-(JP15-Pad9)") (class "Default")
      (node (ref "JP15") (pin "9") (pinfunction "9_9") (pintype "passive"))
    )
    (net (code "89") (name "unconnected-(JP15-Pad10)") (class "Default")
      (node (ref "JP15") (pin "10") (pinfunction "10_10") (pintype "passive"))
    )
    (net (code "90") (name "unconnected-(JP15-Pad11)") (class "Default")
      (node (ref "JP15") (pin "11") (pinfunction "11_11") (pintype "passive"))
    )
    (net (code "91") (name "unconnected-(JP16-Pad1)") (class "Default")
      (node (ref "JP16") (pin "1") (pinfunction "1_1") (pintype "passive"))
    )
    (net (code "92") (name "unconnected-(JP16-Pad2)") (class "Default")
      (node (ref "JP16") (pin "2") (pinfunction "2_2") (pintype "passive"))
    )
    (net (code "93") (name "unconnected-(JP16-Pad3)") (class "Default")
      (node (ref "JP16") (pin "3") (pinfunction "3_3") (pintype "passive"))
    )
    (net (code "94") (name "unconnected-(JP16-Pad4)") (class "Default")
      (node (ref "JP16") (pin "4") (pinfunction "4_4") (pintype "passive"))
    )
    (net (code "95") (name "unconnected-(JP16-Pad5)") (class "Default")
      (node (ref "JP16") (pin "5") (pinfunction "5_5") (pintype "passive"))
    )
    (net (code "96") (name "unconnected-(JP16-Pad6)") (class "Default")
      (node (ref "JP16") (pin "6") (pinfunction "6_6") (pintype "passive"))
    )
    (net (code "97") (name "unconnected-(JP16-Pad7)") (class "Default")
      (node (ref "JP16") (pin "7") (pinfunction "7_7") (pintype "passive"))
    )
    (net (code "98") (name "unconnected-(JP16-Pad8)") (class "Default")
      (node (ref "JP16") (pin "8") (pinfunction "8_8") (pintype "passive"))
    )
    (net (code "99") (name "unconnected-(JP16-Pad9)") (class "Default")
      (node (ref "JP16") (pin "9") (pinfunction "9_9") (pintype "passive"))
    )
    (net (code "100") (name "unconnected-(JP16-Pad10)") (class "Default")
      (node (ref "JP16") (pin "10") (pinfunction "10_10") (pintype "passive"))
    )
    (net (code "101") (name "unconnected-(JP16-Pad11)") (class "Default")
      (node (ref "JP16") (pin "11") (pinfunction "11_11") (pintype "passive"))
    )
    (net (code "102") (name "unconnected-(JP17-Pad1)") (class "Default")
      (node (ref "JP17") (pin "1") (pinfunction "1_1") (pintype "passive"))
    )
    (net (code "103") (name "unconnected-(JP17-Pad2)") (class "Default")
      (node (ref "JP17") (pin "2") (pinfunction "2_2") (pintype "passive"))
    )
    (net (code "104") (name "unconnected-(JP17-Pad3)") (class "Default")
      (node (ref "JP17") (pin "3") (pinfunction "3_3") (pintype "passive"))
    )
    (net (code "105") (name "unconnected-(JP17-Pad4)") (class "Default")
      (node (ref "JP17") (pin "4") (pinfunction "4_4") (pintype "passive"))
    )
    (net (code "106") (name "unconnected-(JP17-Pad5)") (class "Default")
      (node (ref "JP17") (pin "5") (pinfunction "5_5") (pintype "passive"))
    )
    (net (code "107") (name "unconnected-(JP17-Pad6)") (class "Default")
      (node (ref "JP17") (pin "6") (pinfunction "6_6") (pintype "passive"))
    )
    (net (code "108") (name "unconnected-(JP17-Pad7)") (class "Default")
      (node (ref "JP17") (pin "7") (pinfunction "7_7") (pintype "passive"))
    )
    (net (code "109") (name "unconnected-(JP17-Pad8)") (class "Default")
      (node (ref "JP17") (pin "8") (pinfunction "8_8") (pintype "passive"))
    )
    (net (code "110") (name "unconnected-(JP17-Pad9)") (class "Default")
      (node (ref "JP17") (pin "9") (pinfunction "9_9") (pintype "passive"))
    )
    (net (code "111") (name "unconnected-(JP18-Pad1)") (class "Default")
      (node (ref "JP18") (pin "1") (pinfunction "1_1") (pintype "passive"))
    )
    (net (code "112") (name "unconnected-(JP18-Pad2)") (class "Default")
      (node (ref "JP18") (pin "2") (pinfunction "2_2") (pintype "passive"))
    )
    (net (code "113") (name "unconnected-(JP18-Pad3)") (class "Default")
      (node (ref "JP18") (pin "3") (pinfunction "3_3") (pintype "passive"))
    )
    (net (code "114") (name "unconnected-(JP18-Pad4)") (class "Default")
      (node (ref "JP18") (pin "4") (pinfunction "4_4") (pintype "passive"))
    )
    (net (code "115") (name "unconnected-(JP18-Pad5)") (class "Default")
      (node (ref "JP18") (pin "5") (pinfunction "5_5") (pintype "passive"))
    )
    (net (code "116") (name "unconnected-(JP18-Pad6)") (class "Default")
      (node (ref "JP18") (pin "6") (pinfunction "6_6") (pintype "passive"))
    )
    (net (code "117") (name "unconnected-(JP18-Pad7)") (class "Default")
      (node (ref "JP18") (pin "7") (pinfunction "7_7") (pintype "passive"))
    )
    (net (code "118") (name "unconnected-(JP18-Pad8)") (class "Default")
      (node (ref "JP18") (pin "8") (pinfunction "8_8") (pintype "passive"))
    )
    (net (code "119") (name "unconnected-(JP18-Pad9)") (class "Default")
      (node (ref "JP18") (pin "9") (pinfunction "9_9") (pintype "passive"))
    )
    (net (code "120") (name "unconnected-(JP19-Pad1)") (class "Default")
      (node (ref "JP19") (pin "1") (pinfunction "1_1") (pintype "passive"))
    )
    (net (code "121") (name "unconnected-(JP19-Pad2)") (class "Default")
      (node (ref "JP19") (pin "2") (pinfunction "2_2") (pintype "passive"))
    )
    (net (code "122") (name "unconnected-(JP20-Pad1)") (class "Default")
      (node (ref "JP20") (pin "1") (pinfunction "1_1") (pintype "passive"))
    )
    (net (code "123") (name "unconnected-(JP20-Pad2)") (class "Default")
      (node (ref "JP20") (pin "2") (pinfunction "2_2") (pintype "passive"))
    )
    (net (code "124") (name "unconnected-(JP21-Pad1)") (class "Default")
      (node (ref "JP21") (pin "1") (pinfunction "1_1") (pintype "passive"))
    )
    (net (code "125") (name "unconnected-(JP21-Pad2)") (class "Default")
      (node (ref "JP21") (pin "2") (pinfunction "2_2") (pintype "passive"))
    )
    (net (code "126") (name "unconnected-(JP21-Pad3)") (class "Default")
      (node (ref "JP21") (pin "3") (pinfunction "3_3") (pintype "passive"))
    )
    (net (code "127") (name "unconnected-(JP21-Pad4)") (class "Default")
      (node (ref "JP21") (pin "4") (pinfunction "4_4") (pintype "passive"))
    )
    (net (code "128") (name "unconnected-(JP21-Pad5)") (class "Default")
      (node (ref "JP21") (pin "5") (pinfunction "5_5") (pintype "passive"))
    )
    (net (code "129") (name "unconnected-(JP21-Pad6)") (class "Default")
      (node (ref "JP21") (pin "6") (pinfunction "6_6") (pintype "passive"))
    )
    (net (code "130") (name "unconnected-(JP21-Pad7)") (class "Default")
      (node (ref "JP21") (pin "7") (pinfunction "7_7") (pintype "passive"))
    )
    (net (code "131") (name "unconnected-(JP21-Pad8)") (class "Default")
      (node (ref "JP21") (pin "8") (pinfunction "8_8") (pintype "passive"))
    )
    (net (code "132") (name "unconnected-(JP21-Pad9)") (class "Default")
      (node (ref "JP21") (pin "9") (pinfunction "9_9") (pintype "passive"))
    )
    (net (code "133") (name "unconnected-(JP21-Pad10)") (class "Default")
      (node (ref "JP21") (pin "10") (pinfunction "10_10") (pintype "passive"))
    )
    (net (code "134") (name "unconnected-(JP23-Pad1)") (class "Default")
      (node (ref "JP23") (pin "1") (pinfunction "1_1") (pintype "passive"))
    )
    (net (code "135") (name "unconnected-(JP23-Pad2)") (class "Default")
      (node (ref "JP23") (pin "2") (pinfunction "2_2") (pintype "passive"))
    )
    (net (code "136") (name "unconnected-(JP23-Pad3)") (class "Default")
      (node (ref "JP23") (pin "3") (pinfunction "3_3") (pintype "passive"))
    )
    (net (code "137") (name "unconnected-(JP23-Pad4)") (class "Default")
      (node (ref "JP23") (pin "4") (pinfunction "4_4") (pintype "passive"))
    )
    (net (code "138") (name "unconnected-(JP23-Pad5)") (class "Default")
      (node (ref "JP23") (pin "5") (pinfunction "5_5") (pintype "passive"))
    )
    (net (code "139") (name "unconnected-(JP23-Pad6)") (class "Default")
      (node (ref "JP23") (pin "6") (pinfunction "6_6") (pintype "passive"))
    )
    (net (code "140") (name "unconnected-(JP23-Pad7)") (class "Default")
      (node (ref "JP23") (pin "7") (pinfunction "7_7") (pintype "passive"))
    )
    (net (code "141") (name "unconnected-(JP23-Pad8)") (class "Default")
      (node (ref "JP23") (pin "8") (pinfunction "8_8") (pintype "passive"))
    )
    (net (code "142") (name "unconnected-(JP23-Pad9)") (class "Default")
      (node (ref "JP23") (pin "9") (pinfunction "9_9") (pintype "passive"))
    )
    (net (code "143") (name "unconnected-(JP23-Pad10)") (class "Default")
      (node (ref "JP23") (pin "10") (pinfunction "10_10") (pintype "passive"))
    )
    (net (code "144") (name "unconnected-(JP23-Pad11)") (class "Default")
      (node (ref "JP23") (pin "11") (pinfunction "11_11") (pintype "passive"))
    )
    (net (code "145") (name "unconnected-(JP25-Pad1)") (class "Default")
      (node (ref "JP25") (pin "1") (pinfunction "1_1") (pintype "passive"))
    )
    (net (code "146") (name "unconnected-(JP25-Pad2)") (class "Default")
      (node (ref "JP25") (pin "2") (pinfunction "2_2") (pintype "passive"))
    )
    (net (code "147") (name "unconnected-(JP25-Pad3)") (class "Default")
      (node (ref "JP25") (pin "3") (pinfunction "3_3") (pintype "passive"))
    )
    (net (code "148") (name "unconnected-(JP25-Pad4)") (class "Default")
      (node (ref "JP25") (pin "4") (pinfunction "4_4") (pintype "passive"))
    )
    (net (code "149") (name "unconnected-(JP25-Pad5)") (class "Default")
      (node (ref "JP25") (pin "5") (pinfunction "5_5") (pintype "passive"))
    )
    (net (code "150") (name "unconnected-(JP25-Pad6)") (class "Default")
      (node (ref "JP25") (pin "6") (pinfunction "6_6") (pintype "passive"))
    )
    (net (code "151") (name "unconnected-(JP25-Pad7)") (class "Default")
      (node (ref "JP25") (pin "7") (pinfunction "7_7") (pintype "passive"))
    )
    (net (code "152") (name "unconnected-(JP25-Pad8)") (class "Default")
      (node (ref "JP25") (pin "8") (pinfunction "8_8") (pintype "passive"))
    )
    (net (code "153") (name "unconnected-(JP25-Pad9)") (class "Default")
      (node (ref "JP25") (pin "9") (pinfunction "9_9") (pintype "passive"))
    )
    (net (code "154") (name "unconnected-(JP25-Pad10)") (class "Default")
      (node (ref "JP25") (pin "10") (pinfunction "10_10") (pintype "passive"))
    )
    (net (code "155") (name "unconnected-(JP25-Pad11)") (class "Default")
      (node (ref "JP25") (pin "11") (pinfunction "11_11") (pintype "passive"))
    )
    (net (code "156") (name "unconnected-(JP26-Pad1)") (class "Default")
      (node (ref "JP26") (pin "1") (pinfunction "1_1") (pintype "passive"))
    )
    (net (code "157") (name "unconnected-(JP26-Pad2)") (class "Default")
      (node (ref "JP26") (pin "2") (pinfunction "2_2") (pintype "passive"))
    )
    (net (code "158") (name "unconnected-(JP26-Pad3)") (class "Default")
      (node (ref "JP26") (pin "3") (pinfunction "3_3") (pintype "passive"))
    )
    (net (code "159") (name "unconnected-(JP26-Pad4)") (class "Default")
      (node (ref "JP26") (pin "4") (pinfunction "4_4") (pintype "passive"))
    )
    (net (code "160") (name "unconnected-(JP26-Pad5)") (class "Default")
      (node (ref "JP26") (pin "5") (pinfunction "5_5") (pintype "passive"))
    )
    (net (code "161") (name "unconnected-(JP26-Pad6)") (class "Default")
      (node (ref "JP26") (pin "6") (pinfunction "6_6") (pintype "passive"))
    )
    (net (code "162") (name "unconnected-(JP26-Pad7)") (class "Default")
      (node (ref "JP26") (pin "7") (pinfunction "7_7") (pintype "passive"))
    )
    (net (code "163") (name "unconnected-(JP26-Pad8)") (class "Default")
      (node (ref "JP26") (pin "8") (pinfunction "8_8") (pintype "passive"))
    )
    (net (code "164") (name "unconnected-(JP26-Pad9)") (class "Default")
      (node (ref "JP26") (pin "9") (pinfunction "9_9") (pintype "passive"))
    )
    (net (code "165") (name "unconnected-(JP26-Pad10)") (class "Default")
      (node (ref "JP26") (pin "10") (pinfunction "10_10") (pintype "passive"))
    )
    (net (code "166") (name "unconnected-(JP26-Pad11)") (class "Default")
      (node (ref "JP26") (pin "11") (pinfunction "11_11") (pintype "passive"))
    )
    (net (code "167") (name "unconnected-(JP27-Pad1)") (class "Default")
      (node (ref "JP27") (pin "1") (pinfunction "1_1") (pintype "passive"))
    )
    (net (code "168") (name "unconnected-(JP27-Pad2)") (class "Default")
      (node (ref "JP27") (pin "2") (pinfunction "2_2") (pintype "passive"))
    )
    (net (code "169") (name "unconnected-(JP27-Pad3)") (class "Default")
      (node (ref "JP27") (pin "3") (pinfunction "3_3") (pintype "passive"))
    )
    (net (code "170") (name "unconnected-(JP27-Pad4)") (class "Default")
      (node (ref "JP27") (pin "4") (pinfunction "4_4") (pintype "passive"))
    )
    (net (code "171") (name "unconnected-(JP27-Pad5)") (class "Default")
      (node (ref "JP27") (pin "5") (pinfunction "5_5") (pintype "passive"))
    )
    (net (code "172") (name "unconnected-(JP27-Pad6)") (class "Default")
      (node (ref "JP27") (pin "6") (pinfunction "6_6") (pintype "passive"))
    )
    (net (code "173") (name "unconnected-(JP27-Pad7)") (class "Default")
      (node (ref "JP27") (pin "7") (pinfunction "7_7") (pintype "passive"))
    )
    (net (code "174") (name "unconnected-(JP27-Pad8)") (class "Default")
      (node (ref "JP27") (pin "8") (pinfunction "8_8") (pintype "passive"))
    )
    (net (code "175") (name "unconnected-(JP27-Pad9)") (class "Default")
      (node (ref "JP27") (pin "9") (pinfunction "9_9") (pintype "passive"))
    )
    (net (code "176") (name "unconnected-(JP27-Pad10)") (class "Default")
      (node (ref "JP27") (pin "10") (pinfunction "10_10") (pintype "passive"))
    )
    (net (code "177") (name "unconnected-(JP27-Pad11)") (class "Default")
      (node (ref "JP27") (pin "11") (pinfunction "11_11") (pintype "passive"))
    )
    (net (code "178") (name "unconnected-(JP28-Pad1)") (class "Default")
      (node (ref "JP28") (pin "1") (pinfunction "1_1") (pintype "passive"))
    )
    (net (code "179") (name "unconnected-(JP28-Pad2)") (class "Default")
      (node (ref "JP28") (pin "2") (pinfunction "2_2") (pintype "passive"))
    )
    (net (code "180") (name "unconnected-(JP28-Pad3)") (class "Default")
      (node (ref "JP28") (pin "3") (pinfunction "3_3") (pintype "passive"))
    )
    (net (code "181") (name "unconnected-(JP28-Pad4)") (class "Default")
      (node (ref "JP28") (pin "4") (pinfunction "4_4") (pintype "passive"))
    )
    (net (code "182") (name "unconnected-(JP28-Pad5)") (class "Default")
      (node (ref "JP28") (pin "5") (pinfunction "5_5") (pintype "passive"))
    )
    (net (code "183") (name "unconnected-(JP28-Pad6)") (class "Default")
      (node (ref "JP28") (pin "6") (pinfunction "6_6") (pintype "passive"))
    )
    (net (code "184") (name "unconnected-(JP28-Pad7)") (class "Default")
      (node (ref "JP28") (pin "7") (pinfunction "7_7") (pintype "passive"))
    )
    (net (code "185") (name "unconnected-(JP28-Pad8)") (class "Default")
      (node (ref "JP28") (pin "8") (pinfunction "8_8") (pintype "passive"))
    )
    (net (code "186") (name "unconnected-(JP28-Pad9)") (class "Default")
      (node (ref "JP28") (pin "9") (pinfunction "9_9") (pintype "passive"))
    )
    (net (code "187") (name "unconnected-(JP28-Pad10)") (class "Default")
      (node (ref "JP28") (pin "10") (pinfunction "10_10") (pintype "passive"))
    )
    (net (code "188") (name "unconnected-(JP28-Pad11)") (class "Default")
      (node (ref "JP28") (pin "11") (pinfunction "11_11") (pintype "passive"))
    )
    (net (code "189") (name "unconnected-(JP29-Pad1)") (class "Default")
      (node (ref "JP29") (pin "1") (pinfunction "1_1") (pintype "passive"))
    )
    (net (code "190") (name "unconnected-(JP29-Pad2)") (class "Default")
      (node (ref "JP29") (pin "2") (pinfunction "2_2") (pintype "passive"))
    )
    (net (code "191") (name "unconnected-(JP29-Pad3)") (class "Default")
      (node (ref "JP29") (pin "3") (pinfunction "3_3") (pintype "passive"))
    )
    (net (code "192") (name "unconnected-(JP29-Pad4)") (class "Default")
      (node (ref "JP29") (pin "4") (pinfunction "4_4") (pintype "passive"))
    )
    (net (code "193") (name "unconnected-(JP29-Pad5)") (class "Default")
      (node (ref "JP29") (pin "5") (pinfunction "5_5") (pintype "passive"))
    )
    (net (code "194") (name "unconnected-(JP29-Pad6)") (class "Default")
      (node (ref "JP29") (pin "6") (pinfunction "6_6") (pintype "passive"))
    )
    (net (code "195") (name "unconnected-(JP29-Pad7)") (class "Default")
      (node (ref "JP29") (pin "7") (pinfunction "7_7") (pintype "passive"))
    )
    (net (code "196") (name "unconnected-(JP29-Pad8)") (class "Default")
      (node (ref "JP29") (pin "8") (pinfunction "8_8") (pintype "passive"))
    )
    (net (code "197") (name "unconnected-(JP29-Pad9)") (class "Default")
      (node (ref "JP29") (pin "9") (pinfunction "9_9") (pintype "passive"))
    )
    (net (code "198") (name "unconnected-(JP29-Pad10)") (class "Default")
      (node (ref "JP29") (pin "10") (pinfunction "10_10") (pintype "passive"))
    )
    (net (code "199") (name "unconnected-(JP29-Pad11)") (class "Default")
      (node (ref "JP29") (pin "11") (pinfunction "11_11") (pintype "passive"))
    )
    (net (code "200") (name "unconnected-(JP30-Pad1)") (class "Default")
      (node (ref "JP30") (pin "1") (pinfunction "1_1") (pintype "passive"))
    )
    (net (code "201") (name "unconnected-(JP30-Pad2)") (class "Default")
      (node (ref "JP30") (pin "2") (pinfunction "2_2") (pintype "passive"))
    )
    (net (code "202") (name "unconnected-(JP30-Pad3)") (class "Default")
      (node (ref "JP30") (pin "3") (pinfunction "3_3") (pintype "passive"))
    )
    (net (code "203") (name "unconnected-(JP30-Pad4)") (class "Default")
      (node (ref "JP30") (pin "4") (pinfunction "4_4") (pintype "passive"))
    )
    (net (code "204") (name "unconnected-(JP30-Pad5)") (class "Default")
      (node (ref "JP30") (pin "5") (pinfunction "5_5") (pintype "passive"))
    )
    (net (code "205") (name "unconnected-(JP30-Pad6)") (class "Default")
      (node (ref "JP30") (pin "6") (pinfunction "6_6") (pintype "passive"))
    )
    (net (code "206") (name "unconnected-(JP30-Pad7)") (class "Default")
      (node (ref "JP30") (pin "7") (pinfunction "7_7") (pintype "passive"))
    )
    (net (code "207") (name "unconnected-(JP30-Pad8)") (class "Default")
      (node (ref "JP30") (pin "8") (pinfunction "8_8") (pintype "passive"))
    )
    (net (code "208") (name "unconnected-(JP30-Pad9)") (class "Default")
      (node (ref "JP30") (pin "9") (pinfunction "9_9") (pintype "passive"))
    )
    (net (code "209") (name "unconnected-(JP30-Pad10)") (class "Default")
      (node (ref "JP30") (pin "10") (pinfunction "10_10") (pintype "passive"))
    )
    (net (code "210") (name "unconnected-(JP31-Pad1)") (class "Default")
      (node (ref "JP31") (pin "1") (pinfunction "1_1") (pintype "passive"))
    )
    (net (code "211") (name "unconnected-(JP31-Pad2)") (class "Default")
      (node (ref "JP31") (pin "2") (pinfunction "2_2") (pintype "passive"))
    )
    (net (code "212") (name "unconnected-(JP31-Pad3)") (class "Default")
      (node (ref "JP31") (pin "3") (pinfunction "3_3") (pintype "passive"))
    )
    (net (code "213") (name "unconnected-(JP31-Pad4)") (class "Default")
      (node (ref "JP31") (pin "4") (pinfunction "4_4") (pintype "passive"))
    )
    (net (code "214") (name "unconnected-(JP31-Pad5)") (class "Default")
      (node (ref "JP31") (pin "5") (pinfunction "5_5") (pintype "passive"))
    )
    (net (code "215") (name "unconnected-(JP31-Pad6)") (class "Default")
      (node (ref "JP31") (pin "6") (pinfunction "6_6") (pintype "passive"))
    )
    (net (code "216") (name "unconnected-(JP31-Pad7)") (class "Default")
      (node (ref "JP31") (pin "7") (pinfunction "7_7") (pintype "passive"))
    )
    (net (code "217") (name "unconnected-(JP31-Pad8)") (class "Default")
      (node (ref "JP31") (pin "8") (pinfunction "8_8") (pintype "passive"))
    )
    (net (code "218") (name "unconnected-(JP31-Pad9)") (class "Default")
      (node (ref "JP31") (pin "9") (pinfunction "9_9") (pintype "passive"))
    )
    (net (code "219") (name "unconnected-(JP32-Pad1)") (class "Default")
      (node (ref "JP32") (pin "1") (pinfunction "1_1") (pintype "passive"))
    )
    (net (code "220") (name "unconnected-(JP32-Pad2)") (class "Default")
      (node (ref "JP32") (pin "2") (pinfunction "2_2") (pintype "passive"))
    )
    (net (code "221") (name "unconnected-(JP32-Pad3)") (class "Default")
      (node (ref "JP32") (pin "3") (pinfunction "3_3") (pintype "passive"))
    )
    (net (code "222") (name "unconnected-(JP32-Pad4)") (class "Default")
      (node (ref "JP32") (pin "4") (pinfunction "4_4") (pintype "passive"))
    )
    (net (code "223") (name "unconnected-(JP32-Pad5)") (class "Default")
      (node (ref "JP32") (pin "5") (pinfunction "5_5") (pintype "passive"))
    )
    (net (code "224") (name "unconnected-(JP32-Pad6)") (class "Default")
      (node (ref "JP32") (pin "6") (pinfunction "6_6") (pintype "passive"))
    )
    (net (code "225") (name "unconnected-(JP32-Pad7)") (class "Default")
      (node (ref "JP32") (pin "7") (pinfunction "7_7") (pintype "passive"))
    )
    (net (code "226") (name "unconnected-(JP32-Pad8)") (class "Default")
      (node (ref "JP32") (pin "8") (pinfunction "8_8") (pintype "passive"))
    )
    (net (code "227") (name "unconnected-(JP32-Pad9)") (class "Default")
      (node (ref "JP32") (pin "9") (pinfunction "9_9") (pintype "passive"))
    )
    (net (code "228") (name "unconnected-(JP32-Pad10)") (class "Default")
      (node (ref "JP32") (pin "10") (pinfunction "10_10") (pintype "passive"))
    )
    (net (code "229") (name "unconnected-(JP32-Pad11)") (class "Default")
      (node (ref "JP32") (pin "11") (pinfunction "11_11") (pintype "passive"))
    )
    (net (code "230") (name "unconnected-(JP33-Pad1)") (class "Default")
      (node (ref "JP33") (pin "1") (pinfunction "1_1") (pintype "passive"))
    )
    (net (code "231") (name "unconnected-(JP33-Pad2)") (class "Default")
      (node (ref "JP33") (pin "2") (pinfunction "2_2") (pintype "passive"))
    )
    (net (code "232") (name "unconnected-(JP33-Pad3)") (class "Default")
      (node (ref "JP33") (pin "3") (pinfunction "3_3") (pintype "passive"))
    )
    (net (code "233") (name "unconnected-(JP33-Pad4)") (class "Default")
      (node (ref "JP33") (pin "4") (pinfunction "4_4") (pintype "passive"))
    )
    (net (code "234") (name "unconnected-(JP33-Pad5)") (class "Default")
      (node (ref "JP33") (pin "5") (pinfunction "5_5") (pintype "passive"))
    )
    (net (code "235") (name "unconnected-(JP33-Pad6)") (class "Default")
      (node (ref "JP33") (pin "6") (pinfunction "6_6") (pintype "passive"))
    )
    (net (code "236") (name "unconnected-(JP33-Pad7)") (class "Default")
      (node (ref "JP33") (pin "7") (pinfunction "7_7") (pintype "passive"))
    )
    (net (code "237") (name "unconnected-(JP33-Pad8)") (class "Default")
      (node (ref "JP33") (pin "8") (pinfunction "8_8") (pintype "passive"))
    )
    (net (code "238") (name "unconnected-(JP33-Pad9)") (class "Default")
      (node (ref "JP33") (pin "9") (pinfunction "9_9") (pintype "passive"))
    )
    (net (code "239") (name "unconnected-(JP34-Pad1)") (class "Default")
      (node (ref "JP34") (pin "1") (pinfunction "1_1") (pintype "passive"))
    )
    (net (code "240") (name "unconnected-(JP34-Pad2)") (class "Default")
      (node (ref "JP34") (pin "2") (pinfunction "2_2") (pintype "passive"))
    )
    (net (code "241") (name "unconnected-(JP34-Pad3)") (class "Default")
      (node (ref "JP34") (pin "3") (pinfunction "3_3") (pintype "passive"))
    )
    (net (code "242") (name "unconnected-(JP34-Pad4)") (class "Default")
      (node (ref "JP34") (pin "4") (pinfunction "4_4") (pintype "passive"))
    )
    (net (code "243") (name "unconnected-(JP34-Pad5)") (class "Default")
      (node (ref "JP34") (pin "5") (pinfunction "5_5") (pintype "passive"))
    )
    (net (code "244") (name "unconnected-(JP34-Pad6)") (class "Default")
      (node (ref "JP34") (pin "6") (pinfunction "6_6") (pintype "passive"))
    )
    (net (code "245") (name "unconnected-(JP34-Pad7)") (class "Default")
      (node (ref "JP34") (pin "7") (pinfunction "7_7") (pintype "passive"))
    )
    (net (code "246") (name "unconnected-(JP34-Pad8)") (class "Default")
      (node (ref "JP34") (pin "8") (pinfunction "8_8") (pintype "passive"))
    )
    (net (code "247") (name "unconnected-(JP34-Pad9)") (class "Default")
      (node (ref "JP34") (pin "9") (pinfunction "9_9") (pintype "passive"))
    )
    (net (code "248") (name "unconnected-(JP34-Pad10)") (class "Default")
      (node (ref "JP34") (pin "10") (pinfunction "10_10") (pintype "passive"))
    )
    (net (code "249") (name "unconnected-(JP34-Pad11)") (class "Default")
      (node (ref "JP34") (pin "11") (pinfunction "11_11") (pintype "passive"))
    )
    (net (code "250") (name "unconnected-(JP35-Pad1)") (class "Default")
      (node (ref "JP35") (pin "1") (pinfunction "1_1") (pintype "passive"))
    )
    (net (code "251") (name "unconnected-(JP35-Pad2)") (class "Default")
      (node (ref "JP35") (pin "2") (pinfunction "2_2") (pintype "passive"))
    )
    (net (code "252") (name "unconnected-(JP35-Pad3)") (class "Default")
      (node (ref "JP35") (pin "3") (pinfunction "3_3") (pintype "passive"))
    )
    (net (code "253") (name "unconnected-(JP35-Pad4)") (class "Default")
      (node (ref "JP35") (pin "4") (pinfunction "4_4") (pintype "passive"))
    )
    (net (code "254") (name "unconnected-(JP35-Pad5)") (class "Default")
      (node (ref "JP35") (pin "5") (pinfunction "5_5") (pintype "passive"))
    )
    (net (code "255") (name "unconnected-(JP35-Pad6)") (class "Default")
      (node (ref "JP35") (pin "6") (pinfunction "6_6") (pintype "passive"))
    )
    (net (code "256") (name "unconnected-(JP35-Pad7)") (class "Default")
      (node (ref "JP35") (pin "7") (pinfunction "7_7") (pintype "passive"))
    )
    (net (code "257") (name "unconnected-(JP35-Pad8)") (class "Default")
      (node (ref "JP35") (pin "8") (pinfunction "8_8") (pintype "passive"))
    )
    (net (code "258") (name "unconnected-(JP35-Pad9)") (class "Default")
      (node (ref "JP35") (pin "9") (pinfunction "9_9") (pintype "passive"))
    )
    (net (code "259") (name "unconnected-(JP35-Pad10)") (class "Default")
      (node (ref "JP35") (pin "10") (pinfunction "10_10") (pintype "passive"))
    )
    (net (code "260") (name "unconnected-(JP36-Pad1)") (class "Default")
      (node (ref "JP36") (pin "1") (pinfunction "1_1") (pintype "passive"))
    )
    (net (code "261") (name "unconnected-(JP36-Pad2)") (class "Default")
      (node (ref "JP36") (pin "2") (pinfunction "2_2") (pintype "passive"))
    )
    (net (code "262") (name "unconnected-(JP36-Pad3)") (class "Default")
      (node (ref "JP36") (pin "3") (pinfunction "3_3") (pintype "passive"))
    )
    (net (code "263") (name "unconnected-(JP36-Pad4)") (class "Default")
      (node (ref "JP36") (pin "4") (pinfunction "4_4") (pintype "passive"))
    )
    (net (code "264") (name "unconnected-(JP36-Pad5)") (class "Default")
      (node (ref "JP36") (pin "5") (pinfunction "5_5") (pintype "passive"))
    )
    (net (code "265") (name "unconnected-(JP36-Pad6)") (class "Default")
      (node (ref "JP36") (pin "6") (pinfunction "6_6") (pintype "passive"))
    )
    (net (code "266") (name "unconnected-(JP36-Pad7)") (class "Default")
      (node (ref "JP36") (pin "7") (pinfunction "7_7") (pintype "passive"))
    )
    (net (code "267") (name "unconnected-(JP36-Pad8)") (class "Default")
      (node (ref "JP36") (pin "8") (pinfunction "8_8") (pintype "passive"))
    )
    (net (code "268") (name "unconnected-(JP37-Pad1)") (class "Default")
      (node (ref "JP37") (pin "1") (pinfunction "1_1") (pintype "passive"))
    )
    (net (code "269") (name "unconnected-(JP37-Pad2)") (class "Default")
      (node (ref "JP37") (pin "2") (pinfunction "2_2") (pintype "passive"))
    )
    (net (code "270") (name "unconnected-(JP37-Pad3)") (class "Default")
      (node (ref "JP37") (pin "3") (pinfunction "3_3") (pintype "passive"))
    )
    (net (code "271") (name "unconnected-(JP37-Pad4)") (class "Default")
      (node (ref "JP37") (pin "4") (pinfunction "4_4") (pintype "passive"))
    )
    (net (code "272") (name "unconnected-(JP37-Pad5)") (class "Default")
      (node (ref "JP37") (pin "5") (pinfunction "5_5") (pintype "passive"))
    )
    (net (code "273") (name "unconnected-(JP37-Pad6)") (class "Default")
      (node (ref "JP37") (pin "6") (pinfunction "6_6") (pintype "passive"))
    )
    (net (code "274") (name "unconnected-(JP37-Pad7)") (class "Default")
      (node (ref "JP37") (pin "7") (pinfunction "7_7") (pintype "passive"))
    )
    (net (code "275") (name "unconnected-(JP37-Pad8)") (class "Default")
      (node (ref "JP37") (pin "8") (pinfunction "8_8") (pintype "passive"))
    )
    (net (code "276") (name "unconnected-(JP38-Pad1)") (class "Default")
      (node (ref "JP38") (pin "1") (pinfunction "1_1") (pintype "passive"))
    )
    (net (code "277") (name "unconnected-(JP38-Pad2)") (class "Default")
      (node (ref "JP38") (pin "2") (pinfunction "2_2") (pintype "passive"))
    )
    (net (code "278") (name "unconnected-(JP38-Pad3)") (class "Default")
      (node (ref "JP38") (pin "3") (pinfunction "3_3") (pintype "passive"))
    )
    (net (code "279") (name "unconnected-(JP38-Pad4)") (class "Default")
      (node (ref "JP38") (pin "4") (pinfunction "4_4") (pintype "passive"))
    )
    (net (code "280") (name "unconnected-(JP38-Pad5)") (class "Default")
      (node (ref "JP38") (pin "5") (pinfunction "5_5") (pintype "passive"))
    )
    (net (code "281") (name "unconnected-(JP38-Pad6)") (class "Default")
      (node (ref "JP38") (pin "6") (pinfunction "6_6") (pintype "passive"))
    )
    (net (code "282") (name "unconnected-(JP38-Pad7)") (class "Default")
      (node (ref "JP38") (pin "7") (pinfunction "7_7") (pintype "passive"))
    )
    (net (code "283") (name "unconnected-(JP38-Pad8)") (class "Default")
      (node (ref "JP38") (pin "8") (pinfunction "8_8") (pintype "passive"))
    )
    (net (code "284") (name "unconnected-(JP39-Pad1)") (class "Default")
      (node (ref "JP39") (pin "1") (pinfunction "1_1") (pintype "passive"))
    )
    (net (code "285") (name "unconnected-(JP39-Pad2)") (class "Default")
      (node (ref "JP39") (pin "2") (pinfunction "2_2") (pintype "passive"))
    )
    (net (code "286") (name "unconnected-(JP39-Pad3)") (class "Default")
      (node (ref "JP39") (pin "3") (pinfunction "3_3") (pintype "passive"))
    )
    (net (code "287") (name "unconnected-(JP39-Pad4)") (class "Default")
      (node (ref "JP39") (pin "4") (pinfunction "4_4") (pintype "passive"))
    )
    (net (code "288") (name "unconnected-(JP39-Pad5)") (class "Default")
      (node (ref "JP39") (pin "5") (pinfunction "5_5") (pintype "passive"))
    )
    (net (code "289") (name "unconnected-(JP39-Pad6)") (class "Default")
      (node (ref "JP39") (pin "6") (pinfunction "6_6") (pintype "passive"))
    )
    (net (code "290") (name "unconnected-(JP39-Pad7)") (class "Default")
      (node (ref "JP39") (pin "7") (pinfunction "7_7") (pintype "passive"))
    )
    (net (code "291") (name "unconnected-(JP39-Pad8)") (class "Default")
      (node (ref "JP39") (pin "8") (pinfunction "8_8") (pintype "passive"))
    )
    (net (code "292") (name "unconnected-(JP43-Pad1)") (class "Default")
      (node (ref "JP43") (pin "1") (pinfunction "1_1") (pintype "passive"))
    )
    (net (code "293") (name "unconnected-(JP43-Pad2)") (class "Default")
      (node (ref "JP43") (pin "2") (pinfunction "2_2") (pintype "passive"))
    )
    (net (code "294") (name "unconnected-(JP44-Pad1)") (class "Default")
      (node (ref "JP44") (pin "1") (pinfunction "1_1") (pintype "passive"))
    )
    (net (code "295") (name "unconnected-(JP44-Pad2)") (class "Default")
      (node (ref "JP44") (pin "2") (pinfunction "2_2") (pintype "passive"))
    )
    (net (code "296") (name "unconnected-(JP60-Pad1)") (class "Default")
      (node (ref "JP60") (pin "1") (pinfunction "1_1") (pintype "passive"))
    )
    (net (code "297") (name "unconnected-(JP60-Pad2)") (class "Default")
      (node (ref "JP60") (pin "2") (pinfunction "2_2") (pintype "passive"))
    )
  )
)
